# SOC_mcu_v2.net
KiCad netlist of a schematic drawn in EAGLE
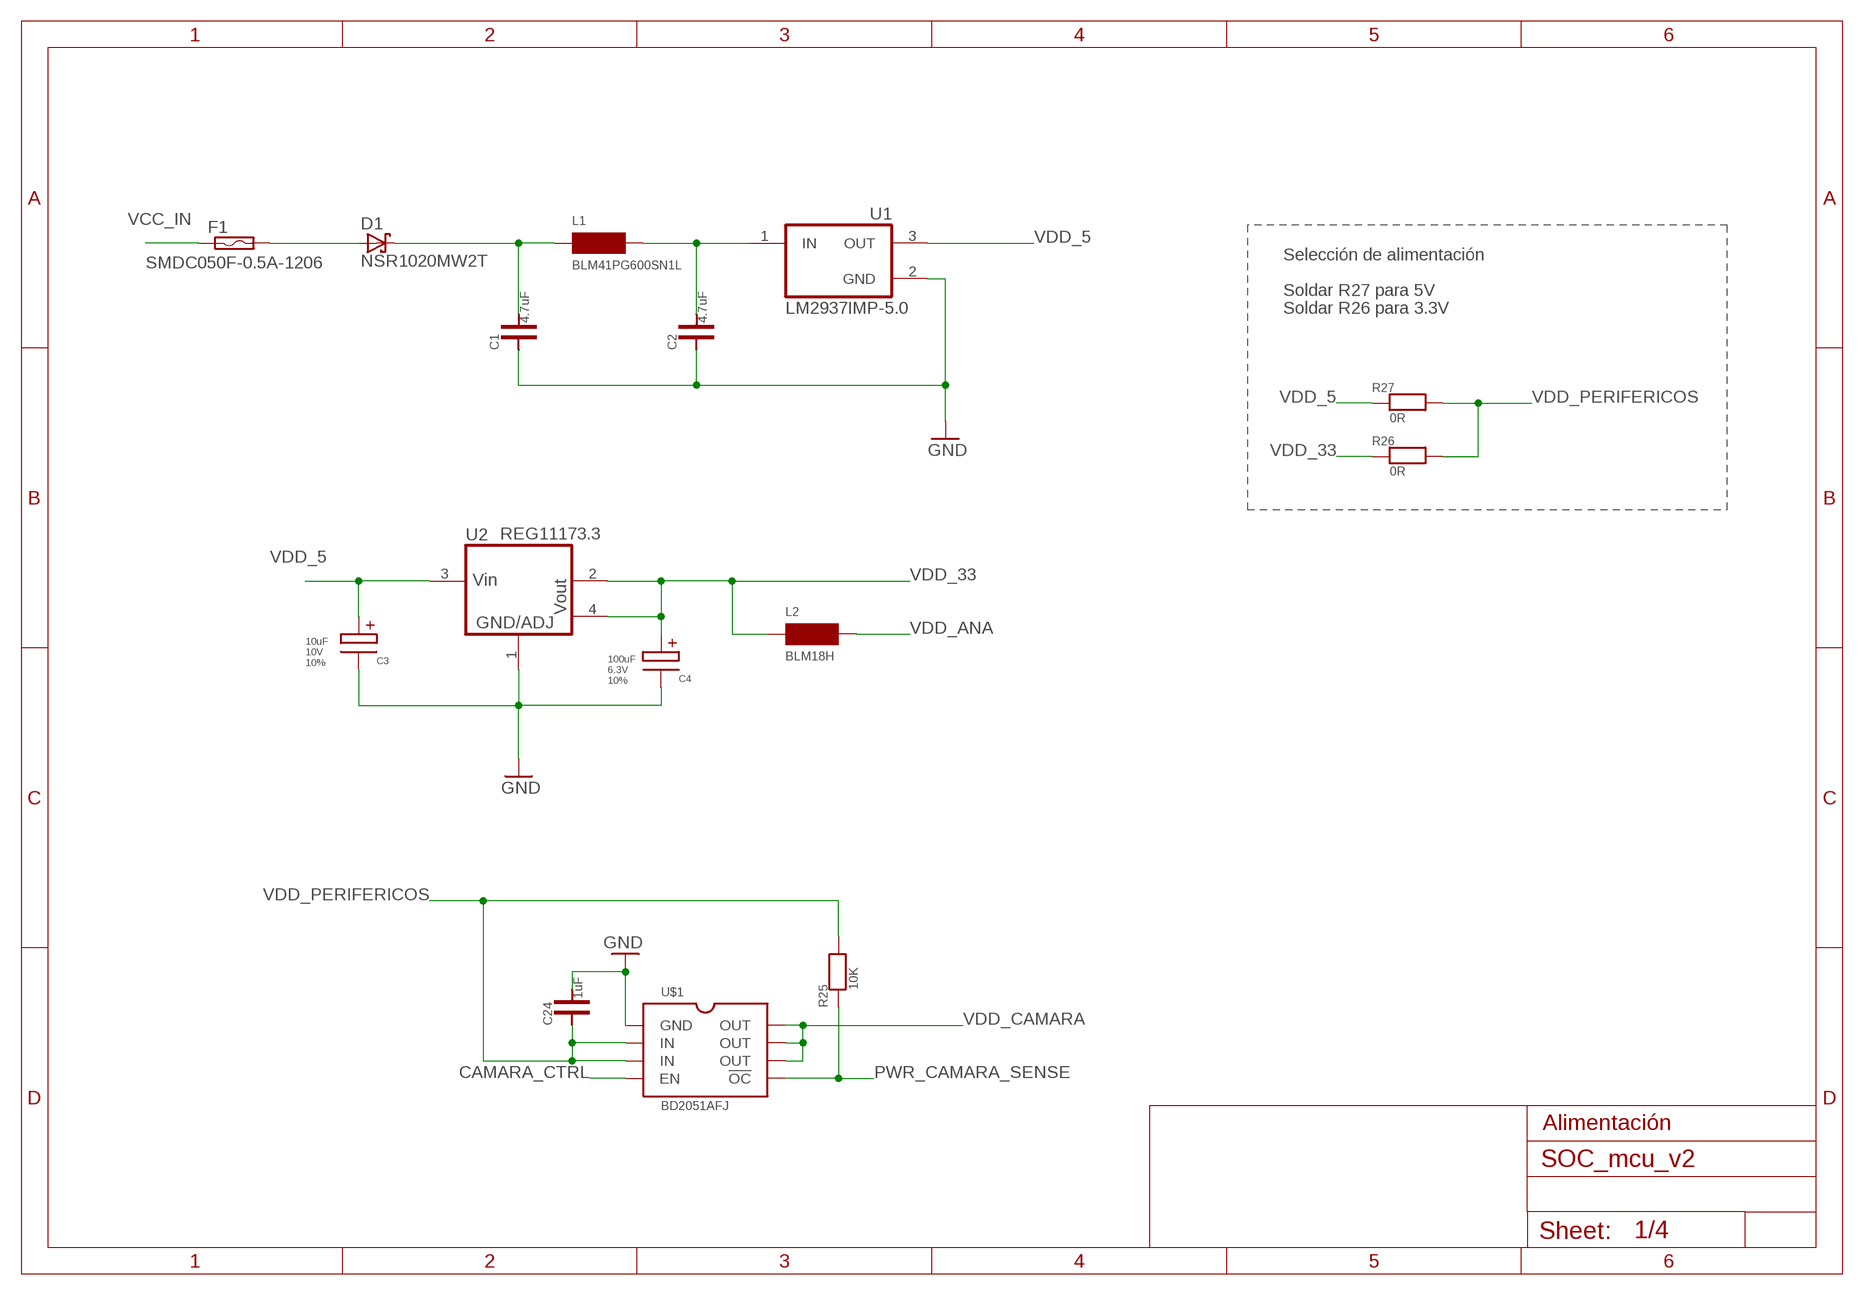
[diagram p0: schematic, sheet 1]
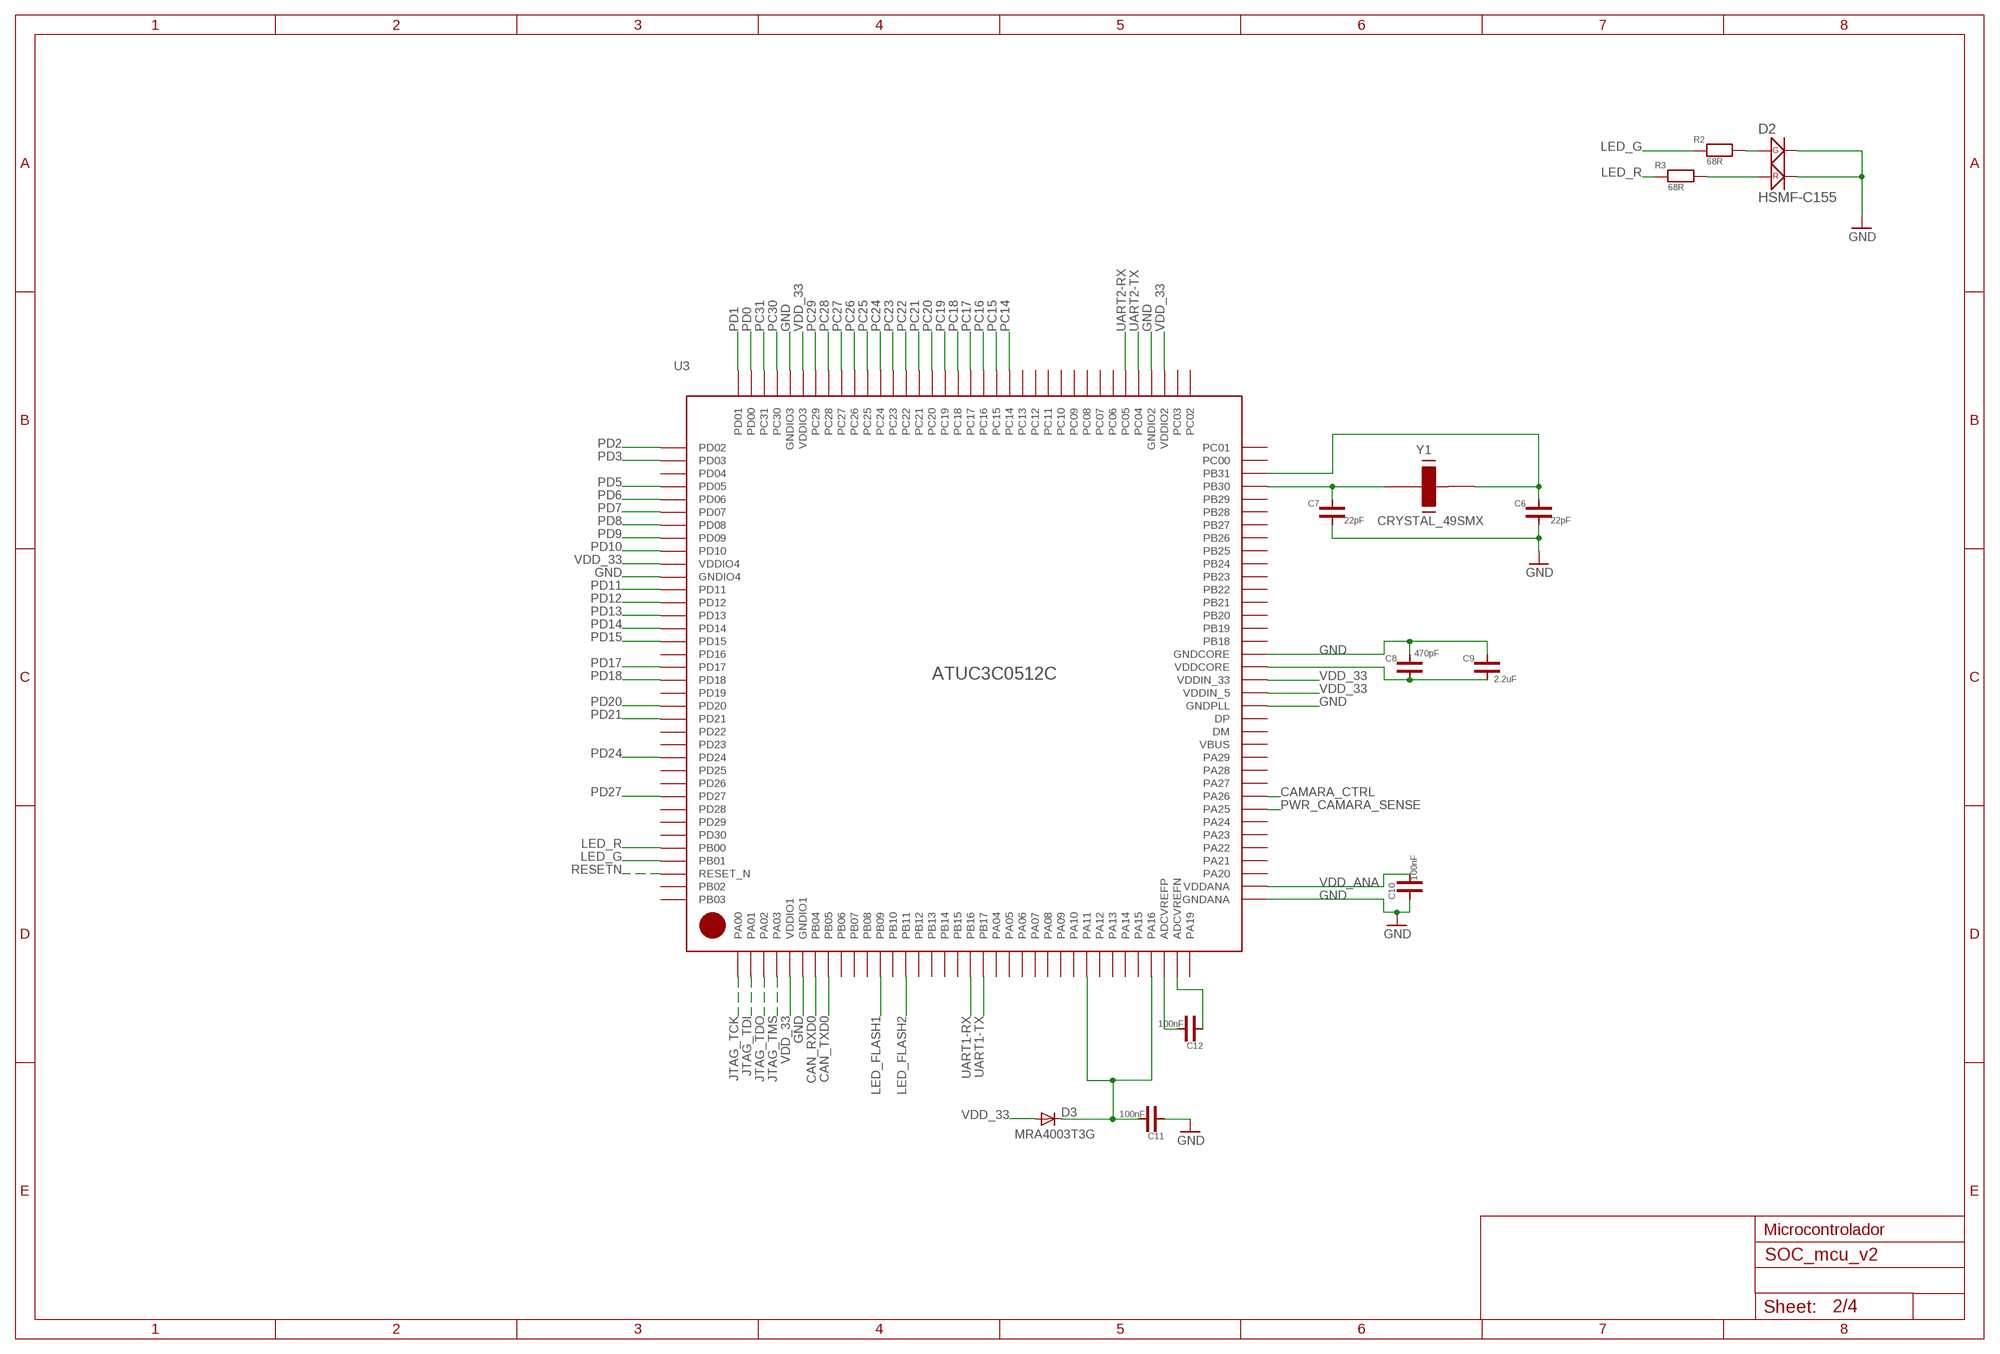
[diagram p1: schematic, sheet 2]
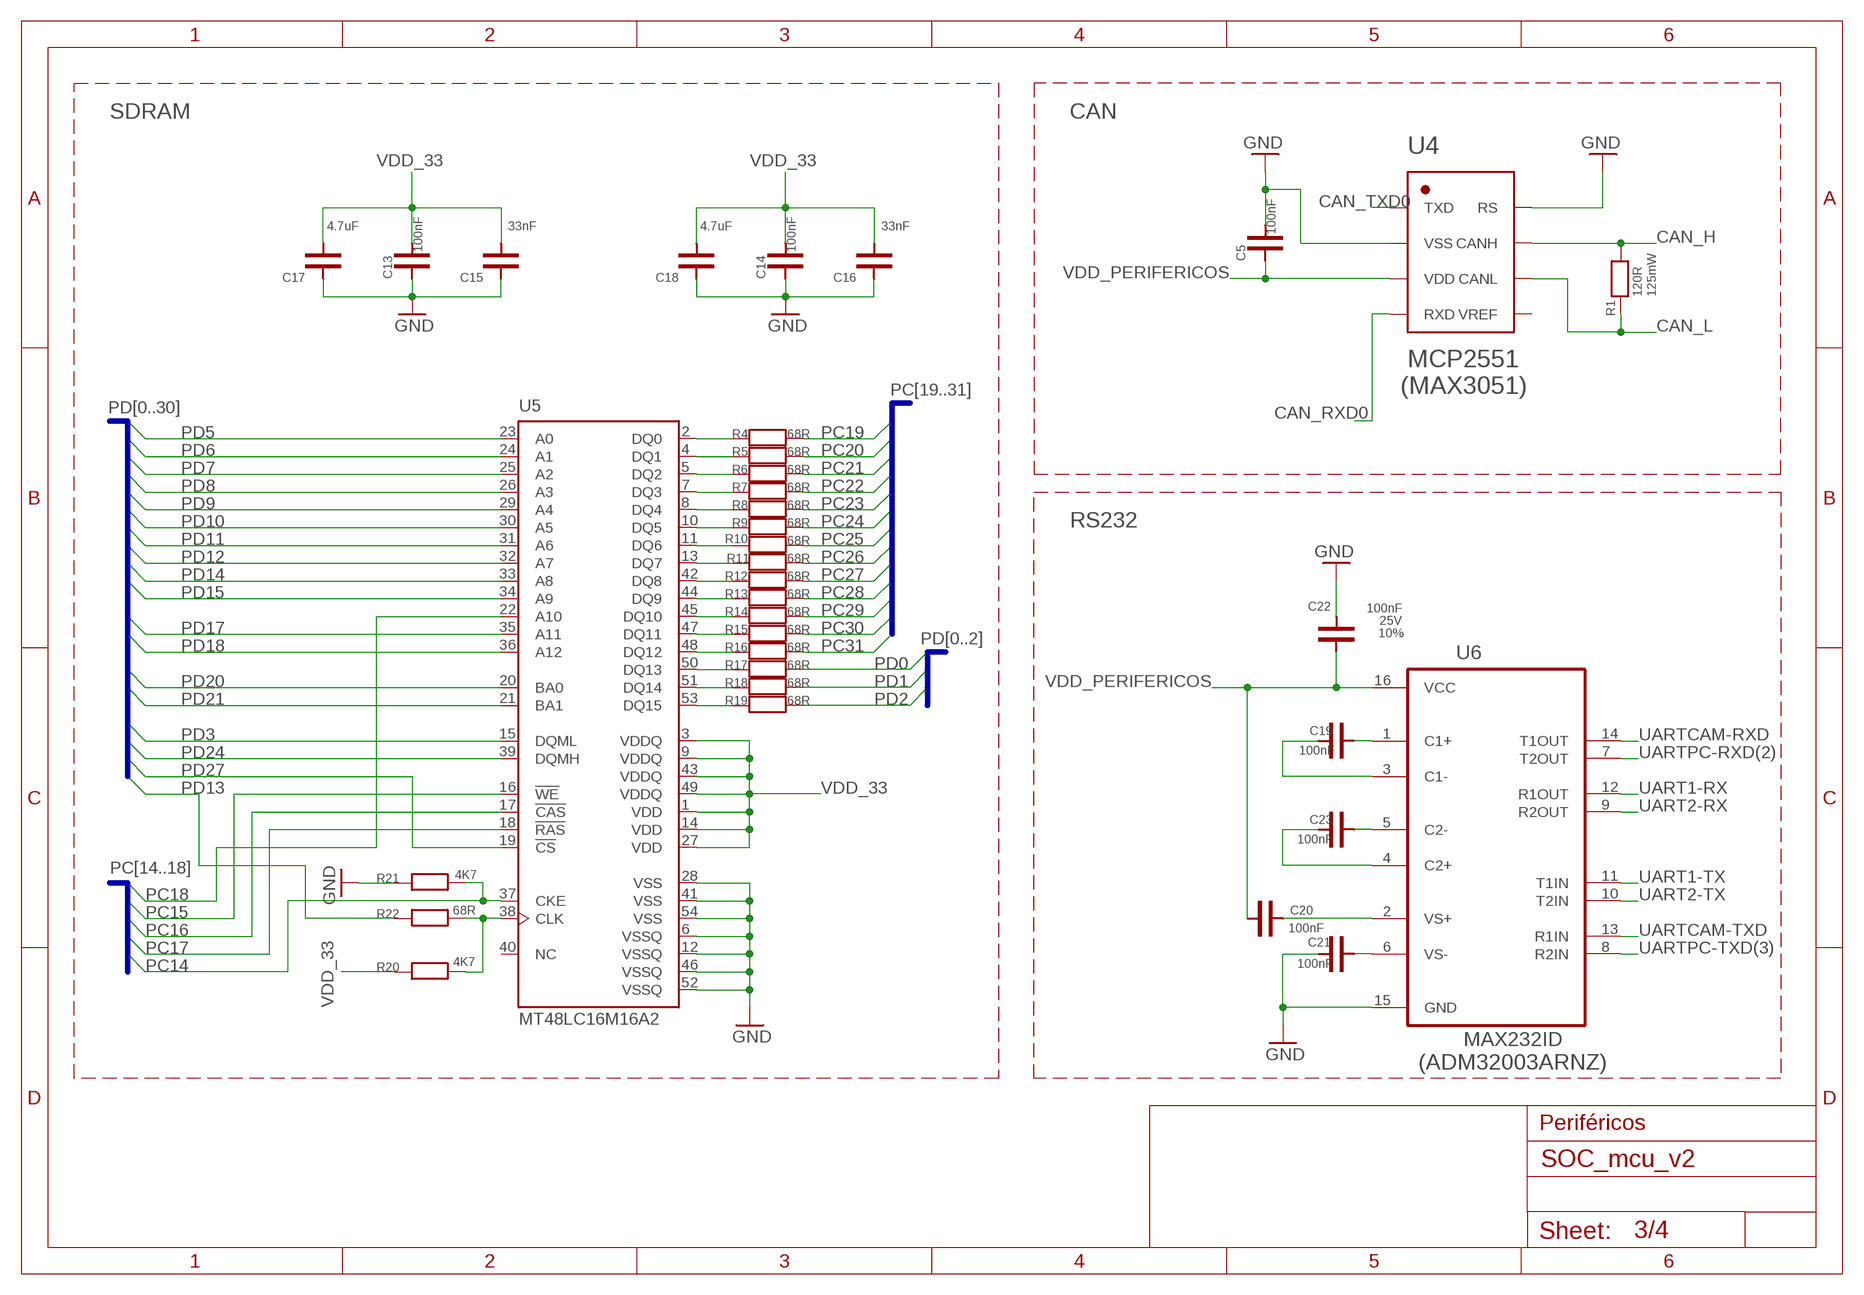
[diagram p2: schematic, sheet 3]
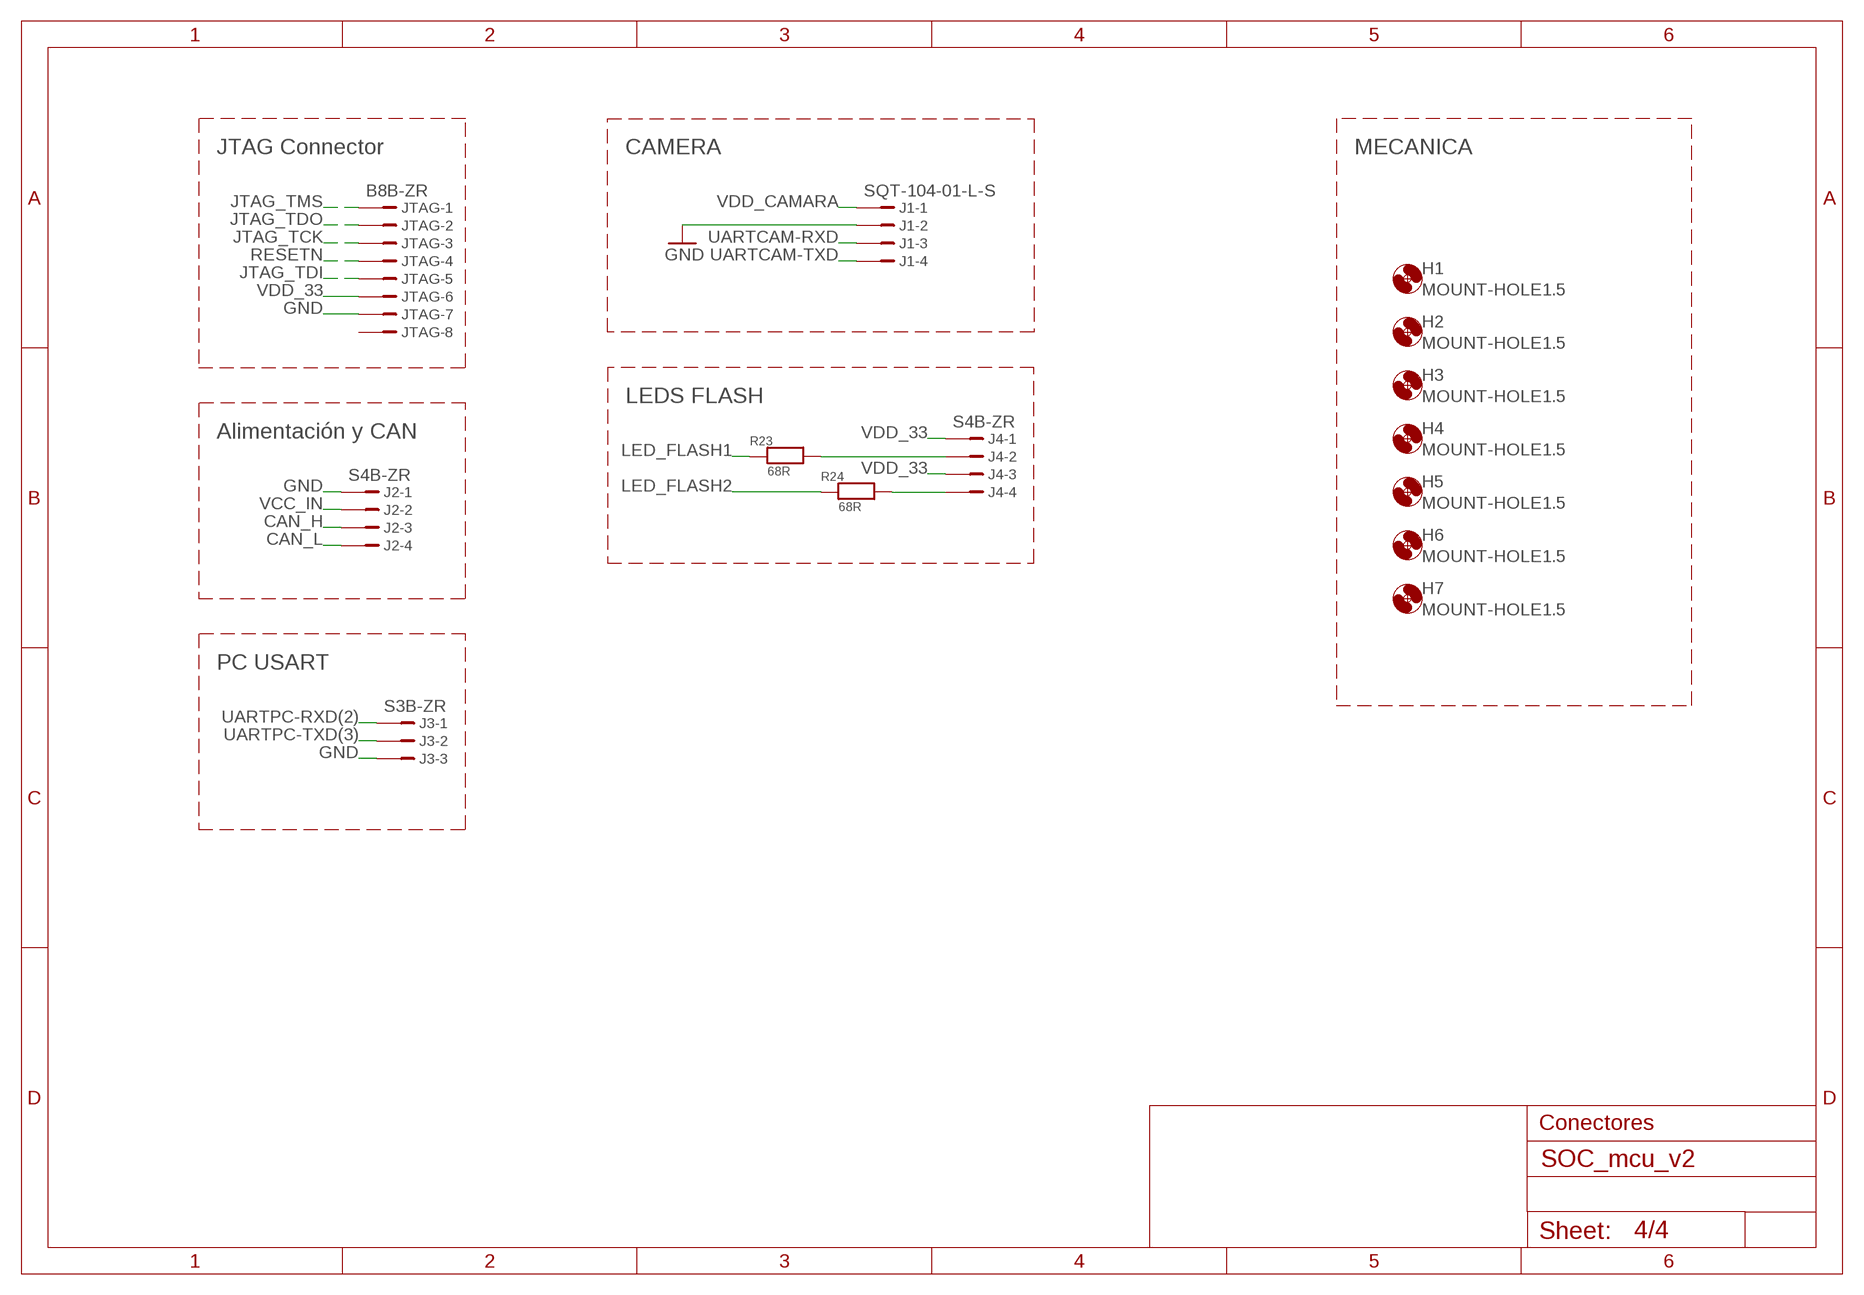
[diagram p3: schematic, sheet 4]

(export (version "E")
  (design (tool "Eeschema 10.0.6"))
  (components
    (comp (ref "C1")
      (value "4.7uF")
      (footprint "eagle-import:C0805")
      (fields (field (name "TOLERANCE") "10%") (field (name "VOLTAGE") "16V"))
      (libsource (lib "eagle-import") (part "C_TF-08054U7-16V-"))
    )
    (comp (ref "C2")
      (value "4.7uF")
      (footprint "eagle-import:C0805")
      (fields (field (name "TOLERANCE") "10%") (field (name "VOLTAGE") "16V"))
      (libsource (lib "eagle-import") (part "C_TF-08054U7-16V-"))
    )
    (comp (ref "C3")
      (value "10uF")
      (footprint "eagle-import:3528-21")
      (fields
        (field (name "MPN") "293D106X9010B2TE3")
        (field (name "TOLERANCE") "10%")
        (field (name "VOLTAGE") "10V")
      )
      (libsource (lib "eagle-import") (part "C293DB10U-10V-10%-"))
    )
    (comp (ref "C4")
      (value "100uF")
      (footprint "eagle-import:3528-21")
      (fields
        (field (name "MPN") "293D107X96R3B2TE3")
        (field (name "TOLERANCE") "10%")
        (field (name "VOLTAGE") "6.3V")
      )
      (libsource (lib "eagle-import") (part "C293DB100U-6V3-10%-"))
    )
    (comp (ref "C24")
      (value "1uF")
      (footprint "eagle-import:C0402")
      (fields (field (name "TOLERANCE") "10%") (field (name "VOLTAGE") "6.3V"))
      (libsource (lib "eagle-import") (part "C_TF-04021U-6.3V-"))
    )
    (comp (ref "D1")
      (value "NSR1020MW2T")
      (footprint "eagle-import:SOD323")
      (fields (field (name "MPN") "NSR1020MW2T1G"))
      (libsource (lib "eagle-import") (part "NSR1020MW2T"))
    )
    (comp (ref "F1")
      (value "SMDC050F-0.5A-1206")
      (footprint "eagle-import:1206")
      (fields
        (field (name "MPN") "NANOSMDC050F/13.2")
        (field (name "MPN_1") "NANOSMDC050F/13.2")
        (field (name "OC_FARNELL") "134-5942")
        (field (name "OC_RS") "138-679")
      )
      (libsource (lib "eagle-import") (part "SMDC050F-12060.5A-"))
    )
    (comp (ref "L1")
      (value "BLM41PG600SN1L")
      (footprint "eagle-import:1806")
      (libsource (lib "eagle-import") (part "BLM41PG600SN1L"))
    )
    (comp (ref "L2")
      (value "BLM18H")
      (footprint "eagle-import:0603")
      (fields (field (name "MPN") "BLM18HG601SN1D"))
      (libsource (lib "eagle-import") (part "BLM18H"))
    )
    (comp (ref "R25")
      (value "10K")
      (footprint "eagle-import:R0402")
      (fields (field (name "POWER") "125mW") (field (name "TOLERANCE") "1%"))
      (libsource (lib "eagle-import") (part "R_TF-040210K-0.125W-1%-"))
    )
    (comp (ref "R26")
      (value "0R")
      (footprint "eagle-import:R0402")
      (fields (field (name "POWER") "62.5mW") (field (name "TOLERANCE") "0.05%"))
      (libsource (lib "eagle-import") (part "R_TF-04020R-0.0625W-0.05%-"))
    )
    (comp (ref "R27")
      (value "0R")
      (footprint "eagle-import:R0402")
      (fields (field (name "POWER") "62.5mW") (field (name "TOLERANCE") "0.05%"))
      (libsource (lib "eagle-import") (part "R_TF-04020R-0.0625W-0.05%-"))
    )
    (comp (ref "U$1")
      (value "BD2051AFJ")
      (footprint "eagle-import:SO08")
      (libsource (lib "eagle-import") (part "BD2051AFJ"))
    )
    (comp (ref "U1")
      (value "LM2937IMP-5.0")
      (footprint "eagle-import:SOT223")
      (libsource (lib "eagle-import") (part "LM2937IMP-5.0"))
    )
    (comp (ref "U2")
      (value "REG11173.3")
      (footprint "eagle-import:SOT223")
      (fields (field (name "MPN") "TLV1117-33CDCY"))
      (libsource (lib "eagle-import") (part "REG11173.3"))
    )
    (comp (ref "C5")
      (value "100nF")
      (footprint "eagle-import:C0402")
      (fields (field (name "TOLERANCE") "10%") (field (name "VOLTAGE") "25V"))
      (libsource (lib "eagle-import") (part "C_TF-0402100N-25V-"))
    )
    (comp (ref "C13")
      (value "100nF")
      (footprint "eagle-import:C0402")
      (fields (field (name "TOLERANCE") "10%") (field (name "VOLTAGE") "25V"))
      (libsource (lib "eagle-import") (part "C_TF-0402100N-25V-"))
    )
    (comp (ref "C14")
      (value "100nF")
      (footprint "eagle-import:C0402")
      (fields (field (name "TOLERANCE") "10%") (field (name "VOLTAGE") "25V"))
      (libsource (lib "eagle-import") (part "C_TF-0402100N-25V-"))
    )
    (comp (ref "C15")
      (value "33nF")
      (footprint "eagle-import:C0402")
      (fields
        (field (name "TOLERANCE") "10%")
        (field (name "VOLTAGE") "25V")
        (field (name "TOLERANCE_1") "10%")
        (field (name "VOLTAGE_1") "25V")
      )
      (libsource (lib "eagle-import") (part "C_TF-040233N-25V-"))
    )
    (comp (ref "C16")
      (value "33nF")
      (footprint "eagle-import:C0402")
      (fields
        (field (name "TOLERANCE") "10%")
        (field (name "VOLTAGE") "25V")
        (field (name "TOLERANCE_1") "10%")
        (field (name "VOLTAGE_1") "25V")
      )
      (libsource (lib "eagle-import") (part "C_TF-040233N-25V-"))
    )
    (comp (ref "C17")
      (value "4.7uF")
      (footprint "eagle-import:C0805")
      (fields
        (field (name "TOLERANCE") "10%")
        (field (name "VOLTAGE") "16V")
        (field (name "TOLERANCE_1") "10%")
        (field (name "VOLTAGE_1") "16V")
      )
      (libsource (lib "eagle-import") (part "C_TF-08054U7-16V-"))
    )
    (comp (ref "C18")
      (value "4.7uF")
      (footprint "eagle-import:C0805")
      (fields
        (field (name "TOLERANCE") "10%")
        (field (name "VOLTAGE") "16V")
        (field (name "TOLERANCE_1") "10%")
        (field (name "VOLTAGE_1") "16V")
      )
      (libsource (lib "eagle-import") (part "C_TF-08054U7-16V-"))
    )
    (comp (ref "C19")
      (value "100nF")
      (footprint "eagle-import:C0402")
      (fields
        (field (name "TOLERANCE") "10%")
        (field (name "VOLTAGE") "25V")
        (field (name "TOLERANCE_1") "10%")
        (field (name "VOLTAGE_1") "25V")
      )
      (libsource (lib "eagle-import") (part "C_TF-0402100N-25V-"))
    )
    (comp (ref "C20")
      (value "100nF")
      (footprint "eagle-import:C0402")
      (fields
        (field (name "TOLERANCE") "10%")
        (field (name "VOLTAGE") "25V")
        (field (name "TOLERANCE_1") "10%")
        (field (name "VOLTAGE_1") "25V")
      )
      (libsource (lib "eagle-import") (part "C_TF-0402100N-25V-"))
    )
    (comp (ref "C21")
      (value "100nF")
      (footprint "eagle-import:C0402")
      (fields
        (field (name "TOLERANCE") "10%")
        (field (name "VOLTAGE") "25V")
        (field (name "OC_FARNELL") "1867948")
        (field (name "OC_RS") "723-5174")
        (field (name "TOLERANCE_1") "10%")
        (field (name "VOLTAGE_1") "25V")
      )
      (libsource (lib "eagle-import") (part "C_TF-0402100N-25V-"))
    )
    (comp (ref "C22")
      (value "100nF")
      (footprint "eagle-import:C0402")
      (fields
        (field (name "TOLERANCE") "10%")
        (field (name "VOLTAGE") "25V")
        (field (name "OC_FARNELL") "1867948")
        (field (name "OC_RS") "723-5174")
        (field (name "TOLERANCE_1") "10%")
        (field (name "VOLTAGE_1") "25V")
      )
      (libsource (lib "eagle-import") (part "C_TF-0402100N-25V-"))
    )
    (comp (ref "C23")
      (value "100nF")
      (footprint "eagle-import:C0402")
      (fields
        (field (name "TOLERANCE") "10%")
        (field (name "VOLTAGE") "25V")
        (field (name "OC_FARNELL") "1867948")
        (field (name "OC_RS") "723-5174")
        (field (name "TOLERANCE_1") "10%")
        (field (name "VOLTAGE_1") "25V")
      )
      (libsource (lib "eagle-import") (part "C_TF-0402100N-25V-"))
    )
    (comp (ref "R1")
      (value "120R")
      (footprint "eagle-import:R0402")
      (fields
        (field (name "POWER") "125mW")
        (field (name "TOLERANCE") "1%")
        (field (name "POWER_1") "125mW")
        (field (name "TOLERANCE_1") "1%")
      )
      (libsource (lib "eagle-import") (part "R_TF-0402120R-0.125W-1%-"))
    )
    (comp (ref "R4")
      (value "68R")
      (footprint "eagle-import:R0402")
      (fields
        (field (name "POWER") "63mW")
        (field (name "TOLERANCE") "5%")
        (field (name "POWER_1") "63mW")
        (field (name "TOLERANCE_1") "5%")
      )
      (libsource (lib "eagle-import") (part "R_TF-040268R-0.063W-5%-"))
    )
    (comp (ref "R5")
      (value "68R")
      (footprint "eagle-import:R0402")
      (fields
        (field (name "POWER") "63mW")
        (field (name "TOLERANCE") "5%")
        (field (name "OC_FARNELL") "1739078")
        (field (name "OC_RS") "678-9535")
        (field (name "POWER_1") "63mW")
        (field (name "TOLERANCE_1") "5%")
      )
      (libsource (lib "eagle-import") (part "R_TF-040268R-0.063W-5%-"))
    )
    (comp (ref "R6")
      (value "68R")
      (footprint "eagle-import:R0402")
      (fields
        (field (name "POWER") "63mW")
        (field (name "TOLERANCE") "5%")
        (field (name "OC_FARNELL") "1739078")
        (field (name "OC_RS") "678-9535")
        (field (name "POWER_1") "63mW")
        (field (name "TOLERANCE_1") "5%")
      )
      (libsource (lib "eagle-import") (part "R_TF-040268R-0.063W-5%-"))
    )
    (comp (ref "R7")
      (value "68R")
      (footprint "eagle-import:R0402")
      (fields
        (field (name "POWER") "63mW")
        (field (name "TOLERANCE") "5%")
        (field (name "OC_FARNELL") "1739078")
        (field (name "OC_RS") "678-9535")
        (field (name "POWER_1") "63mW")
        (field (name "TOLERANCE_1") "5%")
      )
      (libsource (lib "eagle-import") (part "R_TF-040268R-0.063W-5%-"))
    )
    (comp (ref "R8")
      (value "68R")
      (footprint "eagle-import:R0402")
      (fields
        (field (name "POWER") "63mW")
        (field (name "TOLERANCE") "5%")
        (field (name "OC_FARNELL") "1739078")
        (field (name "OC_RS") "678-9535")
        (field (name "POWER_1") "63mW")
        (field (name "TOLERANCE_1") "5%")
      )
      (libsource (lib "eagle-import") (part "R_TF-040268R-0.063W-5%-"))
    )
    (comp (ref "R9")
      (value "68R")
      (footprint "eagle-import:R0402")
      (fields
        (field (name "POWER") "63mW")
        (field (name "TOLERANCE") "5%")
        (field (name "OC_FARNELL") "1739078")
        (field (name "OC_RS") "678-9535")
        (field (name "POWER_1") "63mW")
        (field (name "TOLERANCE_1") "5%")
      )
      (libsource (lib "eagle-import") (part "R_TF-040268R-0.063W-5%-"))
    )
    (comp (ref "R10")
      (value "68R")
      (footprint "eagle-import:R0402")
      (fields
        (field (name "POWER") "63mW")
        (field (name "TOLERANCE") "5%")
        (field (name "OC_FARNELL") "1739078")
        (field (name "OC_RS") "678-9535")
        (field (name "POWER_1") "63mW")
        (field (name "TOLERANCE_1") "5%")
      )
      (libsource (lib "eagle-import") (part "R_TF-040268R-0.063W-5%-"))
    )
    (comp (ref "R11")
      (value "68R")
      (footprint "eagle-import:R0402")
      (fields
        (field (name "POWER") "63mW")
        (field (name "TOLERANCE") "5%")
        (field (name "OC_FARNELL") "1739078")
        (field (name "OC_RS") "678-9535")
        (field (name "POWER_1") "63mW")
        (field (name "TOLERANCE_1") "5%")
      )
      (libsource (lib "eagle-import") (part "R_TF-040268R-0.063W-5%-"))
    )
    (comp (ref "R12")
      (value "68R")
      (footprint "eagle-import:R0402")
      (fields
        (field (name "POWER") "63mW")
        (field (name "TOLERANCE") "5%")
        (field (name "OC_FARNELL") "1739078")
        (field (name "OC_RS") "678-9535")
        (field (name "POWER_1") "63mW")
        (field (name "TOLERANCE_1") "5%")
      )
      (libsource (lib "eagle-import") (part "R_TF-040268R-0.063W-5%-"))
    )
    (comp (ref "R13")
      (value "68R")
      (footprint "eagle-import:R0402")
      (fields
        (field (name "POWER") "63mW")
        (field (name "TOLERANCE") "5%")
        (field (name "OC_FARNELL") "1739078")
        (field (name "OC_RS") "678-9535")
        (field (name "POWER_1") "63mW")
        (field (name "TOLERANCE_1") "5%")
      )
      (libsource (lib "eagle-import") (part "R_TF-040268R-0.063W-5%-"))
    )
    (comp (ref "R14")
      (value "68R")
      (footprint "eagle-import:R0402")
      (fields
        (field (name "POWER") "63mW")
        (field (name "TOLERANCE") "5%")
        (field (name "OC_FARNELL") "1739078")
        (field (name "OC_RS") "678-9535")
        (field (name "POWER_1") "63mW")
        (field (name "TOLERANCE_1") "5%")
      )
      (libsource (lib "eagle-import") (part "R_TF-040268R-0.063W-5%-"))
    )
    (comp (ref "R15")
      (value "68R")
      (footprint "eagle-import:R0402")
      (fields
        (field (name "POWER") "63mW")
        (field (name "TOLERANCE") "5%")
        (field (name "OC_FARNELL") "1739078")
        (field (name "OC_RS") "678-9535")
        (field (name "POWER_1") "63mW")
        (field (name "TOLERANCE_1") "5%")
      )
      (libsource (lib "eagle-import") (part "R_TF-040268R-0.063W-5%-"))
    )
    (comp (ref "R16")
      (value "68R")
      (footprint "eagle-import:R0402")
      (fields
        (field (name "POWER") "63mW")
        (field (name "TOLERANCE") "5%")
        (field (name "OC_FARNELL") "1739078")
        (field (name "OC_RS") "678-9535")
        (field (name "POWER_1") "63mW")
        (field (name "TOLERANCE_1") "5%")
      )
      (libsource (lib "eagle-import") (part "R_TF-040268R-0.063W-5%-"))
    )
    (comp (ref "R17")
      (value "68R")
      (footprint "eagle-import:R0402")
      (fields
        (field (name "POWER") "63mW")
        (field (name "TOLERANCE") "5%")
        (field (name "OC_FARNELL") "1739078")
        (field (name "OC_RS") "678-9535")
        (field (name "POWER_1") "63mW")
        (field (name "TOLERANCE_1") "5%")
      )
      (libsource (lib "eagle-import") (part "R_TF-040268R-0.063W-5%-"))
    )
    (comp (ref "R18")
      (value "68R")
      (footprint "eagle-import:R0402")
      (fields
        (field (name "POWER") "63mW")
        (field (name "TOLERANCE") "5%")
        (field (name "OC_FARNELL") "1739078")
        (field (name "OC_RS") "678-9535")
        (field (name "POWER_1") "63mW")
        (field (name "TOLERANCE_1") "5%")
      )
      (libsource (lib "eagle-import") (part "R_TF-040268R-0.063W-5%-"))
    )
    (comp (ref "R19")
      (value "68R")
      (footprint "eagle-import:R0402")
      (fields
        (field (name "POWER") "63mW")
        (field (name "TOLERANCE") "5%")
        (field (name "OC_FARNELL") "1739078")
        (field (name "OC_RS") "678-9535")
        (field (name "POWER_1") "63mW")
        (field (name "TOLERANCE_1") "5%")
      )
      (libsource (lib "eagle-import") (part "R_TF-040268R-0.063W-5%-"))
    )
    (comp (ref "R20")
      (value "4K7")
      (footprint "eagle-import:R0402")
      (fields
        (field (name "POWER") "125mW")
        (field (name "TOLERANCE") "1%")
        (field (name "POWER_1") "125mW")
        (field (name "TOLERANCE_1") "1%")
      )
      (libsource (lib "eagle-import") (part "R_TF-04024K7-0.125W-1%-"))
    )
    (comp (ref "R21")
      (value "4K7")
      (footprint "eagle-import:R0402")
      (fields
        (field (name "POWER") "125mW")
        (field (name "TOLERANCE") "1%")
        (field (name "POWER_1") "125mW")
        (field (name "TOLERANCE_1") "1%")
      )
      (libsource (lib "eagle-import") (part "R_TF-04024K7-0.125W-1%-"))
    )
    (comp (ref "R22")
      (value "68R")
      (footprint "eagle-import:R0402")
      (fields
        (field (name "POWER") "63mW")
        (field (name "TOLERANCE") "5%")
        (field (name "POWER_1") "63mW")
        (field (name "TOLERANCE_1") "5%")
      )
      (libsource (lib "eagle-import") (part "R_TF-040268R-0.063W-5%-"))
    )
    (comp (ref "U4")
      (value "MCP2551")
      (footprint "eagle-import:SO08")
      (libsource (lib "eagle-import") (part "MCP2551"))
    )
    (comp (ref "U5")
      (value "MT48LC16M16A2")
      (footprint "eagle-import:TSOP54-400")
      (fields (field (name "MPN") "MT48LC16M16A2P-7E:D"))
      (libsource (lib "eagle-import") (part "MT48LC16M16A2"))
    )
    (comp (ref "U6")
      (value "MAX232ID")
      (footprint "eagle-import:SOIC127P600X175-16N")
      (libsource (lib "eagle-import") (part "MAX232ID"))
    )
    (comp (ref "C6")
      (value "22pF")
      (footprint "eagle-import:C0402")
      (fields (field (name "TOLERANCE") "5%") (field (name "VOLTAGE") "50V"))
      (libsource (lib "eagle-import") (part "C_TF-040222P-50V-"))
    )
    (comp (ref "C7")
      (value "22pF")
      (footprint "eagle-import:C0402")
      (fields (field (name "TOLERANCE") "5%") (field (name "VOLTAGE") "50V"))
      (libsource (lib "eagle-import") (part "C_TF-040222P-50V-"))
    )
    (comp (ref "C8")
      (value "470pF")
      (footprint "eagle-import:C0402")
      (fields (field (name "TOLERANCE") "10%") (field (name "VOLTAGE") "50V"))
      (libsource (lib "eagle-import") (part "C_TF-0402470P-50V-"))
    )
    (comp (ref "C9")
      (value "2.2uF")
      (footprint "eagle-import:C0603")
      (fields (field (name "TOLERANCE") "80%") (field (name "VOLTAGE") "16V"))
      (libsource (lib "eagle-import") (part "C_TF-06032U2-16V-"))
    )
    (comp (ref "C10")
      (value "100nF")
      (footprint "eagle-import:C0402")
      (fields (field (name "TOLERANCE") "10%") (field (name "VOLTAGE") "25V"))
      (libsource (lib "eagle-import") (part "C_TF-0402100N-25V-"))
    )
    (comp (ref "C11")
      (value "100nF")
      (footprint "eagle-import:C0402")
      (fields (field (name "TOLERANCE") "10%") (field (name "VOLTAGE") "25V"))
      (libsource (lib "eagle-import") (part "C_TF-0402100N-25V-"))
    )
    (comp (ref "C12")
      (value "100nF")
      (footprint "eagle-import:C0402")
      (fields (field (name "TOLERANCE") "10%") (field (name "VOLTAGE") "25V"))
      (libsource (lib "eagle-import") (part "C_TF-0402100N-25V-"))
    )
    (comp (ref "D2")
      (value "HSMF-C155")
      (footprint "eagle-import:HSMF-C")
      (libsource (lib "eagle-import") (part "HSMF-C155"))
    )
    (comp (ref "D3")
      (value "MRA4003T3G")
      (footprint "eagle-import:SMA")
      (libsource (lib "eagle-import") (part "MRA4003T3G"))
    )
    (comp (ref "R2")
      (value "68R")
      (footprint "eagle-import:R0402")
      (fields (field (name "POWER") "63mW") (field (name "TOLERANCE") "5%"))
      (libsource (lib "eagle-import") (part "R_TF-040268R-0.063W-5%-"))
    )
    (comp (ref "R3")
      (value "68R")
      (footprint "eagle-import:R0402")
      (fields (field (name "POWER") "63mW") (field (name "TOLERANCE") "5%"))
      (libsource (lib "eagle-import") (part "R_TF-040268R-0.063W-5%-"))
    )
    (comp (ref "U3")
      (value "ATUC3C0512C")
      (footprint "eagle-import:TQFP144")
      (fields (field (name "MPN") "AT32UC3C0512C-ALUT "))
      (libsource (lib "eagle-import") (part "ATUC3C0512C"))
    )
    (comp (ref "Y1")
      (value "CRYSTAL_49SMX")
      (footprint "eagle-import:HC49UP")
      (fields (field (name "MPN") "16.000MHZ 49USMX/30/50/40/18PF/ATF"))
      (libsource (lib "eagle-import") (part "CRYSTAL_49SMX"))
    )
    (comp (ref "H1")
      (value "MOUNT-HOLE1.5")
      (footprint "eagle-import:1,5")
      (libsource (lib "eagle-import") (part "MOUNT-HOLE1.5"))
    )
    (comp (ref "H2")
      (value "MOUNT-HOLE1.5")
      (footprint "eagle-import:1,5")
      (libsource (lib "eagle-import") (part "MOUNT-HOLE1.5"))
    )
    (comp (ref "H3")
      (value "MOUNT-HOLE1.5")
      (footprint "eagle-import:1,5")
      (libsource (lib "eagle-import") (part "MOUNT-HOLE1.5"))
    )
    (comp (ref "H4")
      (value "MOUNT-HOLE1.5")
      (footprint "eagle-import:1,5")
      (libsource (lib "eagle-import") (part "MOUNT-HOLE1.5"))
    )
    (comp (ref "H5")
      (value "MOUNT-HOLE1.5")
      (footprint "eagle-import:1,5")
      (libsource (lib "eagle-import") (part "MOUNT-HOLE1.5"))
    )
    (comp (ref "H6")
      (value "MOUNT-HOLE1.5")
      (footprint "eagle-import:1,5")
      (libsource (lib "eagle-import") (part "MOUNT-HOLE1.5"))
    )
    (comp (ref "H7")
      (value "MOUNT-HOLE1.5")
      (footprint "eagle-import:1,5")
      (libsource (lib "eagle-import") (part "MOUNT-HOLE1.5"))
    )
    (comp (ref "J1")
      (value "SQT-104-01-L-S")
      (footprint "eagle-import:THD-SQT-104-01-L-S")
      (libsource (lib "eagle-import") (part "SQT-104-01-L-S"))
    )
    (comp (ref "J2")
      (value "S4B-ZR")
      (footprint "eagle-import:S4B-ZR")
      (libsource (lib "eagle-import") (part "S4B-ZR"))
    )
    (comp (ref "J3")
      (value "S3B-ZR")
      (footprint "eagle-import:S3B-ZR")
      (libsource (lib "eagle-import") (part "S3B-ZR"))
    )
    (comp (ref "J4")
      (value "S4B-ZR")
      (footprint "eagle-import:S4B-ZR")
      (libsource (lib "eagle-import") (part "S4B-ZR"))
    )
    (comp (ref "JTAG")
      (value "B8B-ZR")
      (footprint "eagle-import:B8B-ZR")
      (libsource (lib "eagle-import") (part "B8B-ZR"))
    )
    (comp (ref "R23")
      (value "68R")
      (footprint "eagle-import:R0402")
      (fields (field (name "POWER") "63mW") (field (name "TOLERANCE") "5%"))
      (libsource (lib "eagle-import") (part "R_TF-040268R-0.063W-5%-"))
    )
    (comp (ref "R24")
      (value "68R")
      (footprint "eagle-import:R0402")
      (fields (field (name "POWER") "63mW") (field (name "TOLERANCE") "5%"))
      (libsource (lib "eagle-import") (part "R_TF-040268R-0.063W-5%-"))
    )
  )
  (nets
    (net (code "15") (name "CAMARA_CTRL") (class "Default")
      (node (ref "U$1") (pin "4") (pinfunction "EN_4") (pintype "bidirectional"))
      (node (ref "U3") (pin "45") (pinfunction "PA26_45") (pintype "bidirectional"))
    )
    (net (code "16") (name "CAN_H") (class "Default")
      (node (ref "J2") (pin "3") (pinfunction "1_3") (pintype "passive"))
      (node (ref "R1") (pin "2") (pinfunction "P$2_2") (pintype "bidirectional"))
      (node (ref "U4") (pin "7") (pinfunction "CANH_7") (pintype "bidirectional"))
    )
    (net (code "17") (name "CAN_L") (class "Default")
      (node (ref "J2") (pin "4") (pinfunction "1_4") (pintype "passive"))
      (node (ref "R1") (pin "1") (pinfunction "P$1_1") (pintype "bidirectional"))
      (node (ref "U4") (pin "6") (pinfunction "CANL_6") (pintype "bidirectional"))
    )
    (net (code "18") (name "CAN_RXD0") (class "Default")
      (node (ref "U3") (pin "7") (pinfunction "PB04_7") (pintype "bidirectional"))
      (node (ref "U4") (pin "4") (pinfunction "RXD_4") (pintype "bidirectional"))
    )
    (net (code "19") (name "CAN_TXD0") (class "Default")
      (node (ref "U3") (pin "8") (pinfunction "PB05_8") (pintype "bidirectional"))
      (node (ref "U4") (pin "1") (pinfunction "TXD_1") (pintype "bidirectional"))
    )
    (net (code "20") (name "GND") (class "Default")
      (node (ref "C1") (pin "1") (pinfunction "P$1_1") (pintype "bidirectional"))
      (node (ref "C10") (pin "1") (pinfunction "P$1_1") (pintype "bidirectional"))
      (node (ref "C11") (pin "1") (pinfunction "P$1_1") (pintype "bidirectional"))
      (node (ref "C13") (pin "1") (pinfunction "P$1_1") (pintype "bidirectional"))
      (node (ref "C14") (pin "1") (pinfunction "P$1_1") (pintype "bidirectional"))
      (node (ref "C15") (pin "1") (pinfunction "P$1_1") (pintype "bidirectional"))
      (node (ref "C16") (pin "1") (pinfunction "P$1_1") (pintype "bidirectional"))
      (node (ref "C17") (pin "1") (pinfunction "P$1_1") (pintype "bidirectional"))
      (node (ref "C18") (pin "1") (pinfunction "P$1_1") (pintype "bidirectional"))
      (node (ref "C2") (pin "1") (pinfunction "P$1_1") (pintype "bidirectional"))
      (node (ref "C21") (pin "1") (pinfunction "P$1_1") (pintype "bidirectional"))
      (node (ref "C22") (pin "2") (pinfunction "P$2_2") (pintype "bidirectional"))
      (node (ref "C24") (pin "2") (pinfunction "P$2_2") (pintype "bidirectional"))
      (node (ref "C3") (pin "NEG") (pinfunction "NEG_NEG") (pintype "bidirectional"))
      (node (ref "C4") (pin "NEG") (pinfunction "NEG_NEG") (pintype "bidirectional"))
      (node (ref "C5") (pin "2") (pinfunction "P$2_2") (pintype "bidirectional"))
      (node (ref "C6") (pin "1") (pinfunction "P$1_1") (pintype "bidirectional"))
      (node (ref "C7") (pin "1") (pinfunction "P$1_1") (pintype "bidirectional"))
      (node (ref "C8") (pin "2") (pinfunction "P$2_2") (pintype "bidirectional"))
      (node (ref "C9") (pin "2") (pinfunction "P$2_2") (pintype "bidirectional"))
      (node (ref "D2") (pin "2") (pinfunction "2_2") (pintype "bidirectional"))
      (node (ref "D2") (pin "4") (pinfunction "4_4") (pintype "bidirectional"))
      (node (ref "J1") (pin "2") (pinfunction "1_2") (pintype "passive"))
      (node (ref "J2") (pin "1") (pinfunction "1_1") (pintype "passive"))
      (node (ref "J3") (pin "3") (pinfunction "1_3") (pintype "passive"))
      (node (ref "JTAG") (pin "7") (pinfunction "1_7") (pintype "passive"))
      (node (ref "R21") (pin "1") (pinfunction "P$1_1") (pintype "bidirectional"))
      (node (ref "U$1") (pin "1") (pinfunction "GND_1") (pintype "bidirectional"))
      (node (ref "U1") (pin "2") (pinfunction "GND_2") (pintype "power_in"))
      (node (ref "U2") (pin "1") (pinfunction "GND_1") (pintype "bidirectional"))
      (node (ref "U3") (pin "104") (pinfunction "GNDIO3_104") (pintype "bidirectional"))
      (node (ref "U3") (pin "119") (pinfunction "GNDIO4_119") (pintype "bidirectional"))
      (node (ref "U3") (pin "37") (pinfunction "GNDANA_37") (pintype "bidirectional"))
      (node (ref "U3") (pin "52") (pinfunction "GNDPLL_52") (pintype "bidirectional"))
      (node (ref "U3") (pin "56") (pinfunction "GNDCORE_56") (pintype "bidirectional"))
      (node (ref "U3") (pin "6") (pinfunction "GNDIO1_6") (pintype "bidirectional"))
      (node (ref "U3") (pin "76") (pinfunction "GNDIO2_76") (pintype "bidirectional"))
      (node (ref "U4") (pin "2") (pinfunction "VSS_2") (pintype "bidirectional"))
      (node (ref "U4") (pin "8") (pinfunction "RS_8") (pintype "bidirectional"))
      (node (ref "U5") (pin "12") (pinfunction "VSSQ_12") (pintype "bidirectional"))
      (node (ref "U5") (pin "28") (pinfunction "VSS_28") (pintype "bidirectional"))
      (node (ref "U5") (pin "41") (pinfunction "VSS_41") (pintype "bidirectional"))
      (node (ref "U5") (pin "46") (pinfunction "VSSQ_46") (pintype "bidirectional"))
      (node (ref "U5") (pin "52") (pinfunction "VSSQ_52") (pintype "bidirectional"))
      (node (ref "U5") (pin "54") (pinfunction "VSS_54") (pintype "bidirectional"))
      (node (ref "U5") (pin "6") (pinfunction "VSSQ_6") (pintype "bidirectional"))
      (node (ref "U6") (pin "15") (pinfunction "GND_15") (pintype "passive"))
    )
    (net (code "21") (name "JTAG_TCK") (class "Default")
      (node (ref "JTAG") (pin "3") (pinfunction "1_3") (pintype "passive"))
      (node (ref "U3") (pin "1") (pinfunction "PA00_1") (pintype "bidirectional"))
    )
    (net (code "22") (name "JTAG_TDI") (class "Default")
      (node (ref "JTAG") (pin "5") (pinfunction "1_5") (pintype "passive"))
      (node (ref "U3") (pin "2") (pinfunction "PA01_2") (pintype "bidirectional"))
    )
    (net (code "23") (name "JTAG_TDO") (class "Default")
      (node (ref "JTAG") (pin "2") (pinfunction "1_2") (pintype "passive"))
      (node (ref "U3") (pin "3") (pinfunction "PA02_3") (pintype "bidirectional"))
    )
    (net (code "24") (name "JTAG_TMS") (class "Default")
      (node (ref "JTAG") (pin "1") (pinfunction "1_1") (pintype "passive"))
      (node (ref "U3") (pin "4") (pinfunction "PA03_4") (pintype "bidirectional"))
    )
    (net (code "25") (name "LED_FLASH1") (class "Default")
      (node (ref "R23") (pin "1") (pinfunction "P$1_1") (pintype "bidirectional"))
      (node (ref "U3") (pin "12") (pinfunction "PB09_12") (pintype "bidirectional"))
    )
    (net (code "26") (name "LED_FLASH2") (class "Default")
      (node (ref "R24") (pin "1") (pinfunction "P$1_1") (pintype "bidirectional"))
      (node (ref "U3") (pin "14") (pinfunction "PB11_14") (pintype "bidirectional"))
    )
    (net (code "27") (name "LED_G") (class "Default")
      (node (ref "R2") (pin "1") (pinfunction "P$1_1") (pintype "bidirectional"))
      (node (ref "U3") (pin "141") (pinfunction "PB01_141") (pintype "bidirectional"))
    )
    (net (code "28") (name "LED_R") (class "Default")
      (node (ref "R3") (pin "1") (pinfunction "P$1_1") (pintype "bidirectional"))
      (node (ref "U3") (pin "140") (pinfunction "PB00_140") (pintype "bidirectional"))
    )
    (net (code "29") (name "Net-(C1-P$2)") (class "Default")
      (node (ref "C1") (pin "2") (pinfunction "P$2_2") (pintype "bidirectional"))
      (node (ref "D1") (pin "C") (pinfunction "C_C") (pintype "passive"))
      (node (ref "L1") (pin "P$1") (pinfunction "1_P$1") (pintype "bidirectional"))
    )
    (net (code "30") (name "Net-(C2-P$2)") (class "Default")
      (node (ref "C2") (pin "2") (pinfunction "P$2_2") (pintype "bidirectional"))
      (node (ref "L1") (pin "P$2") (pinfunction "2_P$2") (pintype "bidirectional"))
      (node (ref "U1") (pin "1") (pinfunction "IN_1") (pintype "input"))
    )
    (net (code "31") (name "Net-(C6-P$2)") (class "Default")
      (node (ref "C6") (pin "2") (pinfunction "P$2_2") (pintype "bidirectional"))
      (node (ref "U3") (pin "70") (pinfunction "PB31_70") (pintype "bidirectional"))
      (node (ref "Y1") (pin "2") (pinfunction "2_2") (pintype "bidirectional"))
    )
    (net (code "32") (name "Net-(C7-P$2)") (class "Default")
      (node (ref "C7") (pin "2") (pinfunction "P$2_2") (pintype "bidirectional"))
      (node (ref "U3") (pin "69") (pinfunction "PB30_69") (pintype "bidirectional"))
      (node (ref "Y1") (pin "1") (pinfunction "1_1") (pintype "bidirectional"))
    )
    (net (code "33") (name "Net-(C8-P$1)") (class "Default")
      (node (ref "C8") (pin "1") (pinfunction "P$1_1") (pintype "bidirectional"))
      (node (ref "C9") (pin "1") (pinfunction "P$1_1") (pintype "bidirectional"))
      (node (ref "U3") (pin "55") (pinfunction "VDDCORE_55") (pintype "bidirectional"))
    )
    (net (code "34") (name "Net-(C11-P$2)") (class "Default")
      (node (ref "C11") (pin "2") (pinfunction "P$2_2") (pintype "bidirectional"))
      (node (ref "D3") (pin "C") (pinfunction "C_C") (pintype "passive"))
      (node (ref "U3") (pin "28") (pinfunction "PA11_28") (pintype "bidirectional"))
      (node (ref "U3") (pin "33") (pinfunction "PA16_33") (pintype "bidirectional"))
    )
    (net (code "35") (name "Net-(C12-P$1)") (class "Default")
      (node (ref "C12") (pin "1") (pinfunction "P$1_1") (pintype "bidirectional"))
      (node (ref "U3") (pin "35") (pinfunction "ADCVREFN_35") (pintype "bidirectional"))
    )
    (net (code "36") (name "Net-(C12-P$2)") (class "Default")
      (node (ref "C12") (pin "2") (pinfunction "P$2_2") (pintype "bidirectional"))
      (node (ref "U3") (pin "34") (pinfunction "ADCVREFP_34") (pintype "bidirectional"))
    )
    (net (code "37") (name "Net-(C19-P$1)") (class "Default")
      (node (ref "C19") (pin "1") (pinfunction "P$1_1") (pintype "bidirectional"))
      (node (ref "U6") (pin "3") (pinfunction "C1-_3") (pintype "input"))
    )
    (net (code "38") (name "Net-(C19-P$2)") (class "Default")
      (node (ref "C19") (pin "2") (pinfunction "P$2_2") (pintype "bidirectional"))
      (node (ref "U6") (pin "1") (pinfunction "C1+_1") (pintype "input"))
    )
    (net (code "39") (name "Net-(C20-P$2)") (class "Default")
      (node (ref "C20") (pin "2") (pinfunction "P$2_2") (pintype "bidirectional"))
      (node (ref "U6") (pin "2") (pinfunction "VS+_2") (pintype "input"))
    )
    (net (code "40") (name "Net-(C21-P$2)") (class "Default")
      (node (ref "C21") (pin "2") (pinfunction "P$2_2") (pintype "bidirectional"))
      (node (ref "U6") (pin "6") (pinfunction "VS-_6") (pintype "input"))
    )
    (net (code "41") (name "Net-(C23-P$1)") (class "Default")
      (node (ref "C23") (pin "1") (pinfunction "P$1_1") (pintype "bidirectional"))
      (node (ref "U6") (pin "4") (pinfunction "C2+_4") (pintype "input"))
    )
    (net (code "42") (name "Net-(C23-P$2)") (class "Default")
      (node (ref "C23") (pin "2") (pinfunction "P$2_2") (pintype "bidirectional"))
      (node (ref "U6") (pin "5") (pinfunction "C2-_5") (pintype "input"))
    )
    (net (code "43") (name "Net-(D1-PadA)") (class "Default")
      (node (ref "D1") (pin "A") (pinfunction "A_A") (pintype "passive"))
      (node (ref "F1") (pin "2") (pinfunction "2_2") (pintype "passive"))
    )
    (net (code "44") (name "Net-(J4B-1)") (class "Default")
      (node (ref "J4") (pin "2") (pinfunction "1_2") (pintype "passive"))
      (node (ref "R23") (pin "2") (pinfunction "P$2_2") (pintype "bidirectional"))
    )
    (net (code "45") (name "Net-(J4D-1)") (class "Default")
      (node (ref "J4") (pin "4") (pinfunction "1_4") (pintype "passive"))
      (node (ref "R24") (pin "2") (pinfunction "P$2_2") (pintype "bidirectional"))
    )
    (net (code "46") (name "Net-(R2-P$2)") (class "Default")
      (node (ref "D2") (pin "1") (pinfunction "1_1") (pintype "bidirectional"))
      (node (ref "R2") (pin "2") (pinfunction "P$2_2") (pintype "bidirectional"))
    )
    (net (code "47") (name "Net-(R3-P$2)") (class "Default")
      (node (ref "D2") (pin "3") (pinfunction "3_3") (pintype "bidirectional"))
      (node (ref "R3") (pin "2") (pinfunction "P$2_2") (pintype "bidirectional"))
    )
    (net (code "48") (name "Net-(R4-P$1)") (class "Default")
      (node (ref "R4") (pin "1") (pinfunction "P$1_1") (pintype "bidirectional"))
      (node (ref "U5") (pin "2") (pinfunction "DQ0_2") (pintype "bidirectional"))
    )
    (net (code "49") (name "Net-(R5-P$1)") (class "Default")
      (node (ref "R5") (pin "1") (pinfunction "P$1_1") (pintype "bidirectional"))
      (node (ref "U5") (pin "4") (pinfunction "DQ1_4") (pintype "bidirectional"))
    )
    (net (code "50") (name "Net-(R6-P$1)") (class "Default")
      (node (ref "R6") (pin "1") (pinfunction "P$1_1") (pintype "bidirectional"))
      (node (ref "U5") (pin "5") (pinfunction "DQ2_5") (pintype "bidirectional"))
    )
    (net (code "51") (name "Net-(R7-P$1)") (class "Default")
      (node (ref "R7") (pin "1") (pinfunction "P$1_1") (pintype "bidirectional"))
      (node (ref "U5") (pin "7") (pinfunction "DQ3_7") (pintype "bidirectional"))
    )
    (net (code "52") (name "Net-(R8-P$1)") (class "Default")
      (node (ref "R8") (pin "1") (pinfunction "P$1_1") (pintype "bidirectional"))
      (node (ref "U5") (pin "8") (pinfunction "DQ4_8") (pintype "bidirectional"))
    )
    (net (code "53") (name "Net-(R9-P$1)") (class "Default")
      (node (ref "R9") (pin "1") (pinfunction "P$1_1") (pintype "bidirectional"))
      (node (ref "U5") (pin "10") (pinfunction "DQ5_10") (pintype "bidirectional"))
    )
    (net (code "54") (name "Net-(R10-P$1)") (class "Default")
      (node (ref "R10") (pin "1") (pinfunction "P$1_1") (pintype "bidirectional"))
      (node (ref "U5") (pin "11") (pinfunction "DQ6_11") (pintype "bidirectional"))
    )
    (net (code "55") (name "Net-(R11-P$1)") (class "Default")
      (node (ref "R11") (pin "1") (pinfunction "P$1_1") (pintype "bidirectional"))
      (node (ref "U5") (pin "13") (pinfunction "DQ7_13") (pintype "bidirectional"))
    )
    (net (code "56") (name "Net-(R12-P$1)") (class "Default")
      (node (ref "R12") (pin "1") (pinfunction "P$1_1") (pintype "bidirectional"))
      (node (ref "U5") (pin "42") (pinfunction "DQ8_42") (pintype "bidirectional"))
    )
    (net (code "57") (name "Net-(R13-P$1)") (class "Default")
      (node (ref "R13") (pin "1") (pinfunction "P$1_1") (pintype "bidirectional"))
      (node (ref "U5") (pin "44") (pinfunction "DQ9_44") (pintype "bidirectional"))
    )
    (net (code "58") (name "Net-(R14-P$1)") (class "Default")
      (node (ref "R14") (pin "1") (pinfunction "P$1_1") (pintype "bidirectional"))
      (node (ref "U5") (pin "45") (pinfunction "DQ10_45") (pintype "bidirectional"))
    )
    (net (code "59") (name "Net-(R15-P$1)") (class "Default")
      (node (ref "R15") (pin "1") (pinfunction "P$1_1") (pintype "bidirectional"))
      (node (ref "U5") (pin "47") (pinfunction "DQ11_47") (pintype "bidirectional"))
    )
    (net (code "60") (name "Net-(R16-P$1)") (class "Default")
      (node (ref "R16") (pin "1") (pinfunction "P$1_1") (pintype "bidirectional"))
      (node (ref "U5") (pin "48") (pinfunction "DQ12_48") (pintype "bidirectional"))
    )
    (net (code "61") (name "Net-(R17-P$1)") (class "Default")
      (node (ref "R17") (pin "1") (pinfunction "P$1_1") (pintype "bidirectional"))
      (node (ref "U5") (pin "50") (pinfunction "DQ13_50") (pintype "bidirectional"))
    )
    (net (code "62") (name "Net-(R18-P$1)") (class "Default")
      (node (ref "R18") (pin "1") (pinfunction "P$1_1") (pintype "bidirectional"))
      (node (ref "U5") (pin "51") (pinfunction "DQ14_51") (pintype "bidirectional"))
    )
    (net (code "63") (name "Net-(R19-P$1)") (class "Default")
      (node (ref "R19") (pin "1") (pinfunction "P$1_1") (pintype "bidirectional"))
      (node (ref "U5") (pin "53") (pinfunction "DQ15_53") (pintype "bidirectional"))
    )
    (net (code "64") (name "Net-(R20-P$2)") (class "Default")
      (node (ref "R20") (pin "2") (pinfunction "P$2_2") (pintype "bidirectional"))
      (node (ref "R22") (pin "2") (pinfunction "P$2_2") (pintype "bidirectional"))
      (node (ref "U5") (pin "38") (pinfunction "CLK_38") (pintype "bidirectional"))
    )
    (net (code "65") (name "PC14") (class "Default")
      (node (ref "R21") (pin "2") (pinfunction "P$2_2") (pintype "bidirectional"))
      (node (ref "U3") (pin "87") (pinfunction "PC14_87") (pintype "bidirectional"))
      (node (ref "U5") (pin "37") (pinfunction "CKE_37") (pintype "bidirectional"))
    )
    (net (code "66") (name "PC15") (class "Default")
      (node (ref "U3") (pin "88") (pinfunction "PC15_88") (pintype "bidirectional"))
      (node (ref "U5") (pin "16") (pinfunction "~{WE}_16") (pintype "bidirectional"))
    )
    (net (code "67") (name "PC16") (class "Default")
      (node (ref "U3") (pin "89") (pinfunction "PC16_89") (pintype "bidirectional"))
      (node (ref "U5") (pin "17") (pinfunction "~{CAS}_17") (pintype "bidirectional"))
    )
    (net (code "68") (name "PC17") (class "Default")
      (node (ref "U3") (pin "90") (pinfunction "PC17_90") (pintype "bidirectional"))
      (node (ref "U5") (pin "18") (pinfunction "~{RAS}_18") (pintype "bidirectional"))
    )
    (net (code "69") (name "PC18") (class "Default")
      (node (ref "U3") (pin "91") (pinfunction "PC18_91") (pintype "bidirectional"))
      (node (ref "U5") (pin "22") (pinfunction "A10_22") (pintype "bidirectional"))
    )
    (net (code "70") (name "PC19") (class "Default")
      (node (ref "R4") (pin "2") (pinfunction "P$2_2") (pintype "bidirectional"))
      (node (ref "U3") (pin "92") (pinfunction "PC19_92") (pintype "bidirectional"))
    )
    (net (code "71") (name "PC20") (class "Default")
      (node (ref "R5") (pin "2") (pinfunction "P$2_2") (pintype "bidirectional"))
      (node (ref "U3") (pin "93") (pinfunction "PC20_93") (pintype "bidirectional"))
    )
    (net (code "72") (name "PC21") (class "Default")
      (node (ref "R6") (pin "2") (pinfunction "P$2_2") (pintype "bidirectional"))
      (node (ref "U3") (pin "94") (pinfunction "PC21_94") (pintype "bidirectional"))
    )
    (net (code "73") (name "PC22") (class "Default")
      (node (ref "R7") (pin "2") (pinfunction "P$2_2") (pintype "bidirectional"))
      (node (ref "U3") (pin "95") (pinfunction "PC22_95") (pintype "bidirectional"))
    )
    (net (code "74") (name "PC23") (class "Default")
      (node (ref "R8") (pin "2") (pinfunction "P$2_2") (pintype "bidirectional"))
      (node (ref "U3") (pin "96") (pinfunction "PC23_96") (pintype "bidirectional"))
    )
    (net (code "75") (name "PC24") (class "Default")
      (node (ref "R9") (pin "2") (pinfunction "P$2_2") (pintype "bidirectional"))
      (node (ref "U3") (pin "97") (pinfunction "PC24_97") (pintype "bidirectional"))
    )
    (net (code "76") (name "PC25") (class "Default")
      (node (ref "R10") (pin "2") (pinfunction "P$2_2") (pintype "bidirectional"))
      (node (ref "U3") (pin "98") (pinfunction "PC25_98") (pintype "bidirectional"))
    )
    (net (code "77") (name "PC26") (class "Default")
      (node (ref "R11") (pin "2") (pinfunction "P$2_2") (pintype "bidirectional"))
      (node (ref "U3") (pin "99") (pinfunction "PC26_99") (pintype "bidirectional"))
    )
    (net (code "78") (name "PC27") (class "Default")
      (node (ref "R12") (pin "2") (pinfunction "P$2_2") (pintype "bidirectional"))
      (node (ref "U3") (pin "100") (pinfunction "PC27_100") (pintype "bidirectional"))
    )
    (net (code "79") (name "PC28") (class "Default")
      (node (ref "R13") (pin "2") (pinfunction "P$2_2") (pintype "bidirectional"))
      (node (ref "U3") (pin "101") (pinfunction "PC28_101") (pintype "bidirectional"))
    )
    (net (code "80") (name "PC29") (class "Default")
      (node (ref "R14") (pin "2") (pinfunction "P$2_2") (pintype "bidirectional"))
      (node (ref "U3") (pin "102") (pinfunction "PC29_102") (pintype "bidirectional"))
    )
    (net (code "81") (name "PC30") (class "Default")
      (node (ref "R15") (pin "2") (pinfunction "P$2_2") (pintype "bidirectional"))
      (node (ref "U3") (pin "105") (pinfunction "PC30_105") (pintype "bidirectional"))
    )
    (net (code "82") (name "PC31") (class "Default")
      (node (ref "R16") (pin "2") (pinfunction "P$2_2") (pintype "bidirectional"))
      (node (ref "U3") (pin "106") (pinfunction "PC31_106") (pintype "bidirectional"))
    )
    (net (code "83") (name "PD0") (class "Default")
      (node (ref "R17") (pin "2") (pinfunction "P$2_2") (pintype "bidirectional"))
      (node (ref "U3") (pin "107") (pinfunction "PD00_107") (pintype "bidirectional"))
    )
    (net (code "84") (name "PD1") (class "Default")
      (node (ref "R18") (pin "2") (pinfunction "P$2_2") (pintype "bidirectional"))
      (node (ref "U3") (pin "108") (pinfunction "PD01_108") (pintype "bidirectional"))
    )
    (net (code "85") (name "PD2") (class "Default")
      (node (ref "R19") (pin "2") (pinfunction "P$2_2") (pintype "bidirectional"))
      (node (ref "U3") (pin "109") (pinfunction "PD02_109") (pintype "bidirectional"))
    )
    (net (code "86") (name "PD3") (class "Default")
      (node (ref "U3") (pin "110") (pinfunction "PD03_110") (pintype "bidirectional"))
      (node (ref "U5") (pin "15") (pinfunction "DQML_15") (pintype "bidirectional"))
    )
    (net (code "87") (name "PD5") (class "Default")
      (node (ref "U3") (pin "112") (pinfunction "PD05_112") (pintype "bidirectional"))
      (node (ref "U5") (pin "23") (pinfunction "A0_23") (pintype "bidirectional"))
    )
    (net (code "88") (name "PD6") (class "Default")
      (node (ref "U3") (pin "113") (pinfunction "PD06_113") (pintype "bidirectional"))
      (node (ref "U5") (pin "24") (pinfunction "A1_24") (pintype "bidirectional"))
    )
    (net (code "89") (name "PD7") (class "Default")
      (node (ref "U3") (pin "114") (pinfunction "PD07_114") (pintype "bidirectional"))
      (node (ref "U5") (pin "25") (pinfunction "A2_25") (pintype "bidirectional"))
    )
    (net (code "90") (name "PD8") (class "Default")
      (node (ref "U3") (pin "115") (pinfunction "PD08_115") (pintype "bidirectional"))
      (node (ref "U5") (pin "26") (pinfunction "A3_26") (pintype "bidirectional"))
    )
    (net (code "91") (name "PD9") (class "Default")
      (node (ref "U3") (pin "116") (pinfunction "PD09_116") (pintype "bidirectional"))
      (node (ref "U5") (pin "29") (pinfunction "A4_29") (pintype "bidirectional"))
    )
    (net (code "92") (name "PD10") (class "Default")
      (node (ref "U3") (pin "117") (pinfunction "PD10_117") (pintype "bidirectional"))
      (node (ref "U5") (pin "30") (pinfunction "A5_30") (pintype "bidirectional"))
    )
    (net (code "93") (name "PD11") (class "Default")
      (node (ref "U3") (pin "120") (pinfunction "PD11_120") (pintype "bidirectional"))
      (node (ref "U5") (pin "31") (pinfunction "A6_31") (pintype "bidirectional"))
    )
    (net (code "94") (name "PD12") (class "Default")
      (node (ref "U3") (pin "121") (pinfunction "PD12_121") (pintype "bidirectional"))
      (node (ref "U5") (pin "32") (pinfunction "A7_32") (pintype "bidirectional"))
    )
    (net (code "95") (name "PD13") (class "Default")
      (node (ref "R22") (pin "1") (pinfunction "P$1_1") (pintype "bidirectional"))
      (node (ref "U3") (pin "122") (pinfunction "PD13_122") (pintype "bidirectional"))
    )
    (net (code "96") (name "PD14") (class "Default")
      (node (ref "U3") (pin "123") (pinfunction "PD14_123") (pintype "bidirectional"))
      (node (ref "U5") (pin "33") (pinfunction "A8_33") (pintype "bidirectional"))
    )
    (net (code "97") (name "PD15") (class "Default")
      (node (ref "U3") (pin "124") (pinfunction "PD15_124") (pintype "bidirectional"))
      (node (ref "U5") (pin "34") (pinfunction "A9_34") (pintype "bidirectional"))
    )
    (net (code "98") (name "PD17") (class "Default")
      (node (ref "U3") (pin "126") (pinfunction "PD17_126") (pintype "bidirectional"))
      (node (ref "U5") (pin "35") (pinfunction "A11_35") (pintype "bidirectional"))
    )
    (net (code "99") (name "PD18") (class "Default")
      (node (ref "U3") (pin "127") (pinfunction "PD18_127") (pintype "bidirectional"))
      (node (ref "U5") (pin "36") (pinfunction "A12_36") (pintype "bidirectional"))
    )
    (net (code "100") (name "PD20") (class "Default")
      (node (ref "U3") (pin "129") (pinfunction "PD20_129") (pintype "bidirectional"))
      (node (ref "U5") (pin "20") (pinfunction "BA0_20") (pintype "bidirectional"))
    )
    (net (code "101") (name "PD21") (class "Default")
      (node (ref "U3") (pin "130") (pinfunction "PD21_130") (pintype "bidirectional"))
      (node (ref "U5") (pin "21") (pinfunction "BA1_21") (pintype "bidirectional"))
    )
    (net (code "102") (name "PD24") (class "Default")
      (node (ref "U3") (pin "133") (pinfunction "PD24_133") (pintype "bidirectional"))
      (node (ref "U5") (pin "39") (pinfunction "DQMH_39") (pintype "bidirectional"))
    )
    (net (code "103") (name "PD27") (class "Default")
      (node (ref "U3") (pin "136") (pinfunction "PD27_136") (pintype "bidirectional"))
      (node (ref "U5") (pin "19") (pinfunction "~{CS}_19") (pintype "bidirectional"))
    )
    (net (code "104") (name "PWR_CAMARA_SENSE") (class "Default")
      (node (ref "R25") (pin "1") (pinfunction "P$1_1") (pintype "bidirectional"))
      (node (ref "U$1") (pin "5") (pinfunction "~{OC}_5") (pintype "bidirectional"))
      (node (ref "U3") (pin "44") (pinfunction "PA25_44") (pintype "bidirectional"))
    )
    (net (code "105") (name "RESETN") (class "Default")
      (node (ref "JTAG") (pin "4") (pinfunction "1_4") (pintype "passive"))
      (node (ref "U3") (pin "142") (pinfunction "RESET_N_142") (pintype "bidirectional"))
    )
    (net (code "106") (name "UART1-RX") (class "Default")
      (node (ref "U3") (pin "19") (pinfunction "PB16_19") (pintype "bidirectional"))
      (node (ref "U6") (pin "12") (pinfunction "R1OUT_12") (pintype "output"))
    )
    (net (code "107") (name "UART1-TX") (class "Default")
      (node (ref "U3") (pin "20") (pinfunction "PB17_20") (pintype "bidirectional"))
      (node (ref "U6") (pin "11") (pinfunction "T1IN_11") (pintype "input"))
    )
    (net (code "108") (name "UART2-RX") (class "Default")
      (node (ref "U3") (pin "78") (pinfunction "PC05_78") (pintype "bidirectional"))
      (node (ref "U6") (pin "9") (pinfunction "R2OUT_9") (pintype "output"))
    )
    (net (code "109") (name "UART2-TX") (class "Default")
      (node (ref "U3") (pin "77") (pinfunction "PC04_77") (pintype "bidirectional"))
      (node (ref "U6") (pin "10") (pinfunction "T2IN_10") (pintype "input"))
    )
    (net (code "110") (name "UARTCAM-RXD") (class "Default")
      (node (ref "J1") (pin "3") (pinfunction "1_3") (pintype "passive"))
      (node (ref "U6") (pin "14") (pinfunction "T1OUT_14") (pintype "output"))
    )
    (net (code "111") (name "UARTCAM-TXD") (class "Default")
      (node (ref "J1") (pin "4") (pinfunction "1_4") (pintype "passive"))
      (node (ref "U6") (pin "13") (pinfunction "R1IN_13") (pintype "input"))
    )
    (net (code "112") (name "UARTPC-RXD(2)") (class "Default")
      (node (ref "J3") (pin "1") (pinfunction "1_1") (pintype "passive"))
      (node (ref "U6") (pin "7") (pinfunction "T2OUT_7") (pintype "output"))
    )
    (net (code "113") (name "UARTPC-TXD(3)") (class "Default")
      (node (ref "J3") (pin "2") (pinfunction "1_2") (pintype "passive"))
      (node (ref "U6") (pin "8") (pinfunction "R2IN_8") (pintype "input"))
    )
    (net (code "114") (name "VCC_IN") (class "Default")
      (node (ref "F1") (pin "1") (pinfunction "1_1") (pintype "passive"))
      (node (ref "J2") (pin "2") (pinfunction "1_2") (pintype "passive"))
    )
    (net (code "115") (name "VDD_5") (class "Default")
      (node (ref "C3") (pin "POS") (pinfunction "POS_POS") (pintype "bidirectional"))
      (node (ref "R27") (pin "1") (pinfunction "P$1_1") (pintype "bidirectional"))
      (node (ref "U1") (pin "3") (pinfunction "OUT_3") (pintype "output"))
      (node (ref "U2") (pin "3") (pinfunction "VIN_3") (pintype "input"))
    )
    (net (code "116") (name "VDD_33") (class "Default")
      (node (ref "C13") (pin "2") (pinfunction "P$2_2") (pintype "bidirectional"))
      (node (ref "C14") (pin "2") (pinfunction "P$2_2") (pintype "bidirectional"))
      (node (ref "C15") (pin "2") (pinfunction "P$2_2") (pintype "bidirectional"))
      (node (ref "C16") (pin "2") (pinfunction "P$2_2") (pintype "bidirectional"))
      (node (ref "C17") (pin "2") (pinfunction "P$2_2") (pintype "bidirectional"))
      (node (ref "C18") (pin "2") (pinfunction "P$2_2") (pintype "bidirectional"))
      (node (ref "C4") (pin "POS") (pinfunction "POS_POS") (pintype "bidirectional"))
      (node (ref "D3") (pin "A") (pinfunction "A_A") (pintype "passive"))
      (node (ref "J4") (pin "1") (pinfunction "1_1") (pintype "passive"))
      (node (ref "J4") (pin "3") (pinfunction "1_3") (pintype "passive"))
      (node (ref "JTAG") (pin "6") (pinfunction "1_6") (pintype "passive"))
      (node (ref "L2") (pin "1") (pinfunction "1_1") (pintype "bidirectional"))
      (node (ref "R20") (pin "1") (pinfunction "P$1_1") (pintype "bidirectional"))
      (node (ref "R26") (pin "1") (pinfunction "P$1_1") (pintype "bidirectional"))
      (node (ref "U2") (pin "2") (pinfunction "VOUT_2") (pintype "bidirectional"))
      (node (ref "U2") (pin "4") (pinfunction "VO2_4") (pintype "bidirectional"))
      (node (ref "U3") (pin "103") (pinfunction "VDDIO3_103") (pintype "bidirectional"))
      (node (ref "U3") (pin "118") (pinfunction "VDDIO4_118") (pintype "bidirectional"))
      (node (ref "U3") (pin "5") (pinfunction "VDDIO1_5") (pintype "bidirectional"))
      (node (ref "U3") (pin "53") (pinfunction "VDDIN_5_53") (pintype "bidirectional"))
      (node (ref "U3") (pin "54") (pinfunction "VDDIN_33_54") (pintype "bidirectional"))
      (node (ref "U3") (pin "75") (pinfunction "VDDIO2_75") (pintype "bidirectional"))
      (node (ref "U5") (pin "1") (pinfunction "VDD_1") (pintype "bidirectional"))
      (node (ref "U5") (pin "14") (pinfunction "VDD_14") (pintype "bidirectional"))
      (node (ref "U5") (pin "27") (pinfunction "VDD_27") (pintype "bidirectional"))
      (node (ref "U5") (pin "3") (pinfunction "VDDQ_3") (pintype "bidirectional"))
      (node (ref "U5") (pin "43") (pinfunction "VDDQ_43") (pintype "bidirectional"))
      (node (ref "U5") (pin "49") (pinfunction "VDDQ_49") (pintype "bidirectional"))
      (node (ref "U5") (pin "9") (pinfunction "VDDQ_9") (pintype "bidirectional"))
    )
    (net (code "117") (name "VDD_ANA") (class "Default")
      (node (ref "C10") (pin "2") (pinfunction "P$2_2") (pintype "bidirectional"))
      (node (ref "L2") (pin "2") (pinfunction "2_2") (pintype "bidirectional"))
      (node (ref "U3") (pin "38") (pinfunction "VDDANA_38") (pintype "bidirectional"))
    )
    (net (code "118") (name "VDD_CAMARA") (class "Default")
      (node (ref "J1") (pin "1") (pinfunction "1_1") (pintype "passive"))
      (node (ref "U$1") (pin "6") (pinfunction "OUT_6") (pintype "bidirectional"))
      (node (ref "U$1") (pin "7") (pinfunction "OUT_7") (pintype "bidirectional"))
      (node (ref "U$1") (pin "8") (pinfunction "OUT_8") (pintype "bidirectional"))
    )
    (net (code "119") (name "VDD_PERIFERICOS") (class "Default")
      (node (ref "C20") (pin "1") (pinfunction "P$1_1") (pintype "bidirectional"))
      (node (ref "C22") (pin "1") (pinfunction "P$1_1") (pintype "bidirectional"))
      (node (ref "C24") (pin "1") (pinfunction "P$1_1") (pintype "bidirectional"))
      (node (ref "C5") (pin "1") (pinfunction "P$1_1") (pintype "bidirectional"))
      (node (ref "R25") (pin "2") (pinfunction "P$2_2") (pintype "bidirectional"))
      (node (ref "R26") (pin "2") (pinfunction "P$2_2") (pintype "bidirectional"))
      (node (ref "R27") (pin "2") (pinfunction "P$2_2") (pintype "bidirectional"))
      (node (ref "U$1") (pin "2") (pinfunction "IN_2") (pintype "bidirectional"))
      (node (ref "U$1") (pin "3") (pinfunction "IN_3") (pintype "bidirectional"))
      (node (ref "U4") (pin "3") (pinfunction "VDD_3") (pintype "bidirectional"))
      (node (ref "U6") (pin "16") (pinfunction "VCC_16") (pintype "power_in"))
    )
    (net (code "120") (name "unconnected-(JTAGH-1-Pad8)") (class "Default")
      (node (ref "JTAG") (pin "8") (pinfunction "1_8") (pintype "passive"))
    )
    (net (code "121") (name "unconnected-(U3-DM-Pad50)") (class "Default")
      (node (ref "U3") (pin "50") (pinfunction "DM_50") (pintype "bidirectional"))
    )
    (net (code "122") (name "unconnected-(U3-DP-Pad51)") (class "Default")
      (node (ref "U3") (pin "51") (pinfunction "DP_51") (pintype "bidirectional"))
    )
    (net (code "123") (name "unconnected-(U3-PA04-Pad21)") (class "Default")
      (node (ref "U3") (pin "21") (pinfunction "PA04_21") (pintype "bidirectional"))
    )
    (net (code "124") (name "unconnected-(U3-PA05-Pad22)") (class "Default")
      (node (ref "U3") (pin "22") (pinfunction "PA05_22") (pintype "bidirectional"))
    )
    (net (code "125") (name "unconnected-(U3-PA06-Pad23)") (class "Default")
      (node (ref "U3") (pin "23") (pinfunction "PA06_23") (pintype "bidirectional"))
    )
    (net (code "126") (name "unconnected-(U3-PA07-Pad24)") (class "Default")
      (node (ref "U3") (pin "24") (pinfunction "PA07_24") (pintype "bidirectional"))
    )
    (net (code "127") (name "unconnected-(U3-PA08-Pad25)") (class "Default")
      (node (ref "U3") (pin "25") (pinfunction "PA08_25") (pintype "bidirectional"))
    )
    (net (code "128") (name "unconnected-(U3-PA09-Pad26)") (class "Default")
      (node (ref "U3") (pin "26") (pinfunction "PA09_26") (pintype "bidirectional"))
    )
    (net (code "129") (name "unconnected-(U3-PA10-Pad27)") (class "Default")
      (node (ref "U3") (pin "27") (pinfunction "PA10_27") (pintype "bidirectional"))
    )
    (net (code "130") (name "unconnected-(U3-PA12-Pad29)") (class "Default")
      (node (ref "U3") (pin "29") (pinfunction "PA12_29") (pintype "bidirectional"))
    )
    (net (code "131") (name "unconnected-(U3-PA13-Pad30)") (class "Default")
      (node (ref "U3") (pin "30") (pinfunction "PA13_30") (pintype "bidirectional"))
    )
    (net (code "132") (name "unconnected-(U3-PA14-Pad31)") (class "Default")
      (node (ref "U3") (pin "31") (pinfunction "PA14_31") (pintype "bidirectional"))
    )
    (net (code "133") (name "unconnected-(U3-PA15-Pad32)") (class "Default")
      (node (ref "U3") (pin "32") (pinfunction "PA15_32") (pintype "bidirectional"))
    )
    (net (code "134") (name "unconnected-(U3-PA19-Pad36)") (class "Default")
      (node (ref "U3") (pin "36") (pinfunction "PA19_36") (pintype "bidirectional"))
    )
    (net (code "135") (name "unconnected-(U3-PA20-Pad39)") (class "Default")
      (node (ref "U3") (pin "39") (pinfunction "PA20_39") (pintype "bidirectional"))
    )
    (net (code "136") (name "unconnected-(U3-PA21-Pad40)") (class "Default")
      (node (ref "U3") (pin "40") (pinfunction "PA21_40") (pintype "bidirectional"))
    )
    (net (code "137") (name "unconnected-(U3-PA22-Pad41)") (class "Default")
      (node (ref "U3") (pin "41") (pinfunction "PA22_41") (pintype "bidirectional"))
    )
    (net (code "138") (name "unconnected-(U3-PA23-Pad42)") (class "Default")
      (node (ref "U3") (pin "42") (pinfunction "PA23_42") (pintype "bidirectional"))
    )
    (net (code "139") (name "unconnected-(U3-PA24-Pad43)") (class "Default")
      (node (ref "U3") (pin "43") (pinfunction "PA24_43") (pintype "bidirectional"))
    )
    (net (code "140") (name "unconnected-(U3-PA27-Pad46)") (class "Default")
      (node (ref "U3") (pin "46") (pinfunction "PA27_46") (pintype "bidirectional"))
    )
    (net (code "141") (name "unconnected-(U3-PA28-Pad47)") (class "Default")
      (node (ref "U3") (pin "47") (pinfunction "PA28_47") (pintype "bidirectional"))
    )
    (net (code "142") (name "unconnected-(U3-PA29-Pad48)") (class "Default")
      (node (ref "U3") (pin "48") (pinfunction "PA29_48") (pintype "bidirectional"))
    )
    (net (code "143") (name "unconnected-(U3-PB02-Pad143)") (class "Default")
      (node (ref "U3") (pin "143") (pinfunction "PB02_143") (pintype "bidirectional"))
    )
    (net (code "144") (name "unconnected-(U3-PB03-Pad144)") (class "Default")
      (node (ref "U3") (pin "144") (pinfunction "PB03_144") (pintype "bidirectional"))
    )
    (net (code "145") (name "unconnected-(U3-PB06-Pad9)") (class "Default")
      (node (ref "U3") (pin "9") (pinfunction "PB06_9") (pintype "bidirectional"))
    )
    (net (code "146") (name "unconnected-(U3-PB07-Pad10)") (class "Default")
      (node (ref "U3") (pin "10") (pinfunction "PB07_10") (pintype "bidirectional"))
    )
    (net (code "147") (name "unconnected-(U3-PB08-Pad11)") (class "Default")
      (node (ref "U3") (pin "11") (pinfunction "PB08_11") (pintype "bidirectional"))
    )
    (net (code "148") (name "unconnected-(U3-PB10-Pad13)") (class "Default")
      (node (ref "U3") (pin "13") (pinfunction "PB10_13") (pintype "bidirectional"))
    )
    (net (code "149") (name "unconnected-(U3-PB12-Pad15)") (class "Default")
      (node (ref "U3") (pin "15") (pinfunction "PB12_15") (pintype "bidirectional"))
    )
    (net (code "150") (name "unconnected-(U3-PB13-Pad16)") (class "Default")
      (node (ref "U3") (pin "16") (pinfunction "PB13_16") (pintype "bidirectional"))
    )
    (net (code "151") (name "unconnected-(U3-PB14-Pad17)") (class "Default")
      (node (ref "U3") (pin "17") (pinfunction "PB14_17") (pintype "bidirectional"))
    )
    (net (code "152") (name "unconnected-(U3-PB15-Pad18)") (class "Default")
      (node (ref "U3") (pin "18") (pinfunction "PB15_18") (pintype "bidirectional"))
    )
    (net (code "153") (name "unconnected-(U3-PB18-Pad57)") (class "Default")
      (node (ref "U3") (pin "57") (pinfunction "PB18_57") (pintype "bidirectional"))
    )
    (net (code "154") (name "unconnected-(U3-PB19-Pad58)") (class "Default")
      (node (ref "U3") (pin "58") (pinfunction "PB19_58") (pintype "bidirectional"))
    )
    (net (code "155") (name "unconnected-(U3-PB20-Pad59)") (class "Default")
      (node (ref "U3") (pin "59") (pinfunction "PB20_59") (pintype "bidirectional"))
    )
    (net (code "156") (name "unconnected-(U3-PB21-Pad60)") (class "Default")
      (node (ref "U3") (pin "60") (pinfunction "PB21_60") (pintype "bidirectional"))
    )
    (net (code "157") (name "unconnected-(U3-PB22-Pad61)") (class "Default")
      (node (ref "U3") (pin "61") (pinfunction "PB22_61") (pintype "bidirectional"))
    )
    (net (code "158") (name "unconnected-(U3-PB23-Pad62)") (class "Default")
      (node (ref "U3") (pin "62") (pinfunction "PB23_62") (pintype "bidirectional"))
    )
    (net (code "159") (name "unconnected-(U3-PB24-Pad63)") (class "Default")
      (node (ref "U3") (pin "63") (pinfunction "PB24_63") (pintype "bidirectional"))
    )
    (net (code "160") (name "unconnected-(U3-PB25-Pad64)") (class "Default")
      (node (ref "U3") (pin "64") (pinfunction "PB25_64") (pintype "bidirectional"))
    )
    (net (code "161") (name "unconnected-(U3-PB26-Pad65)") (class "Default")
      (node (ref "U3") (pin "65") (pinfunction "PB26_65") (pintype "bidirectional"))
    )
    (net (code "162") (name "unconnected-(U3-PB27-Pad66)") (class "Default")
      (node (ref "U3") (pin "66") (pinfunction "PB27_66") (pintype "bidirectional"))
    )
    (net (code "163") (name "unconnected-(U3-PB28-Pad67)") (class "Default")
      (node (ref "U3") (pin "67") (pinfunction "PB28_67") (pintype "bidirectional"))
    )
    (net (code "164") (name "unconnected-(U3-PB29-Pad68)") (class "Default")
      (node (ref "U3") (pin "68") (pinfunction "PB29_68") (pintype "bidirectional"))
    )
    (net (code "165") (name "unconnected-(U3-PC00-Pad71)") (class "Default")
      (node (ref "U3") (pin "71") (pinfunction "PC00_71") (pintype "bidirectional"))
    )
    (net (code "166") (name "unconnected-(U3-PC01-Pad72)") (class "Default")
      (node (ref "U3") (pin "72") (pinfunction "PC01_72") (pintype "bidirectional"))
    )
    (net (code "167") (name "unconnected-(U3-PC02-Pad73)") (class "Default")
      (node (ref "U3") (pin "73") (pinfunction "PC02_73") (pintype "bidirectional"))
    )
    (net (code "168") (name "unconnected-(U3-PC03-Pad74)") (class "Default")
      (node (ref "U3") (pin "74") (pinfunction "PC03_74") (pintype "bidirectional"))
    )
    (net (code "169") (name "unconnected-(U3-PC06-Pad79)") (class "Default")
      (node (ref "U3") (pin "79") (pinfunction "PC06_79") (pintype "bidirectional"))
    )
    (net (code "170") (name "unconnected-(U3-PC07-Pad80)") (class "Default")
      (node (ref "U3") (pin "80") (pinfunction "PC07_80") (pintype "bidirectional"))
    )
    (net (code "171") (name "unconnected-(U3-PC08-Pad81)") (class "Default")
      (node (ref "U3") (pin "81") (pinfunction "PC08_81") (pintype "bidirectional"))
    )
    (net (code "172") (name "unconnected-(U3-PC09-Pad82)") (class "Default")
      (node (ref "U3") (pin "82") (pinfunction "PC09_82") (pintype "bidirectional"))
    )
    (net (code "173") (name "unconnected-(U3-PC10-Pad83)") (class "Default")
      (node (ref "U3") (pin "83") (pinfunction "PC10_83") (pintype "bidirectional"))
    )
    (net (code "174") (name "unconnected-(U3-PC11-Pad84)") (class "Default")
      (node (ref "U3") (pin "84") (pinfunction "PC11_84") (pintype "bidirectional"))
    )
    (net (code "175") (name "unconnected-(U3-PC12-Pad85)") (class "Default")
      (node (ref "U3") (pin "85") (pinfunction "PC12_85") (pintype "bidirectional"))
    )
    (net (code "176") (name "unconnected-(U3-PC13-Pad86)") (class "Default")
      (node (ref "U3") (pin "86") (pinfunction "PC13_86") (pintype "bidirectional"))
    )
    (net (code "177") (name "unconnected-(U3-PD04-Pad111)") (class "Default")
      (node (ref "U3") (pin "111") (pinfunction "PD04_111") (pintype "bidirectional"))
    )
    (net (code "178") (name "unconnected-(U3-PD16-Pad125)") (class "Default")
      (node (ref "U3") (pin "125") (pinfunction "PD16_125") (pintype "bidirectional"))
    )
    (net (code "179") (name "unconnected-(U3-PD19-Pad128)") (class "Default")
      (node (ref "U3") (pin "128") (pinfunction "PD19_128") (pintype "bidirectional"))
    )
    (net (code "180") (name "unconnected-(U3-PD22-Pad131)") (class "Default")
      (node (ref "U3") (pin "131") (pinfunction "PD22_131") (pintype "bidirectional"))
    )
    (net (code "181") (name "unconnected-(U3-PD23-Pad132)") (class "Default")
      (node (ref "U3") (pin "132") (pinfunction "PD23_132") (pintype "bidirectional"))
    )
    (net (code "182") (name "unconnected-(U3-PD25-Pad134)") (class "Default")
      (node (ref "U3") (pin "134") (pinfunction "PD25_134") (pintype "bidirectional"))
    )
    (net (code "183") (name "unconnected-(U3-PD26-Pad135)") (class "Default")
      (node (ref "U3") (pin "135") (pinfunction "PD26_135") (pintype "bidirectional"))
    )
    (net (code "184") (name "unconnected-(U3-PD28-Pad137)") (class "Default")
      (node (ref "U3") (pin "137") (pinfunction "PD28_137") (pintype "bidirectional"))
    )
    (net (code "185") (name "unconnected-(U3-PD29-Pad138)") (class "Default")
      (node (ref "U3") (pin "138") (pinfunction "PD29_138") (pintype "bidirectional"))
    )
    (net (code "186") (name "unconnected-(U3-PD30-Pad139)") (class "Default")
      (node (ref "U3") (pin "139") (pinfunction "PD30_139") (pintype "bidirectional"))
    )
    (net (code "187") (name "unconnected-(U3-VBUS-Pad49)") (class "Default")
      (node (ref "U3") (pin "49") (pinfunction "VBUS_49") (pintype "bidirectional"))
    )
    (net (code "188") (name "unconnected-(U4-VREF-Pad5)") (class "Default")
      (node (ref "U4") (pin "5") (pinfunction "VREF_5") (pintype "bidirectional"))
    )
    (net (code "189") (name "unconnected-(U5-NC-Pad40)") (class "Default")
      (node (ref "U5") (pin "40") (pinfunction "NC_40") (pintype "bidirectional"))
    )
  )
)
